# board0.net
KiCad netlist of a schematic drawn in EAGLE
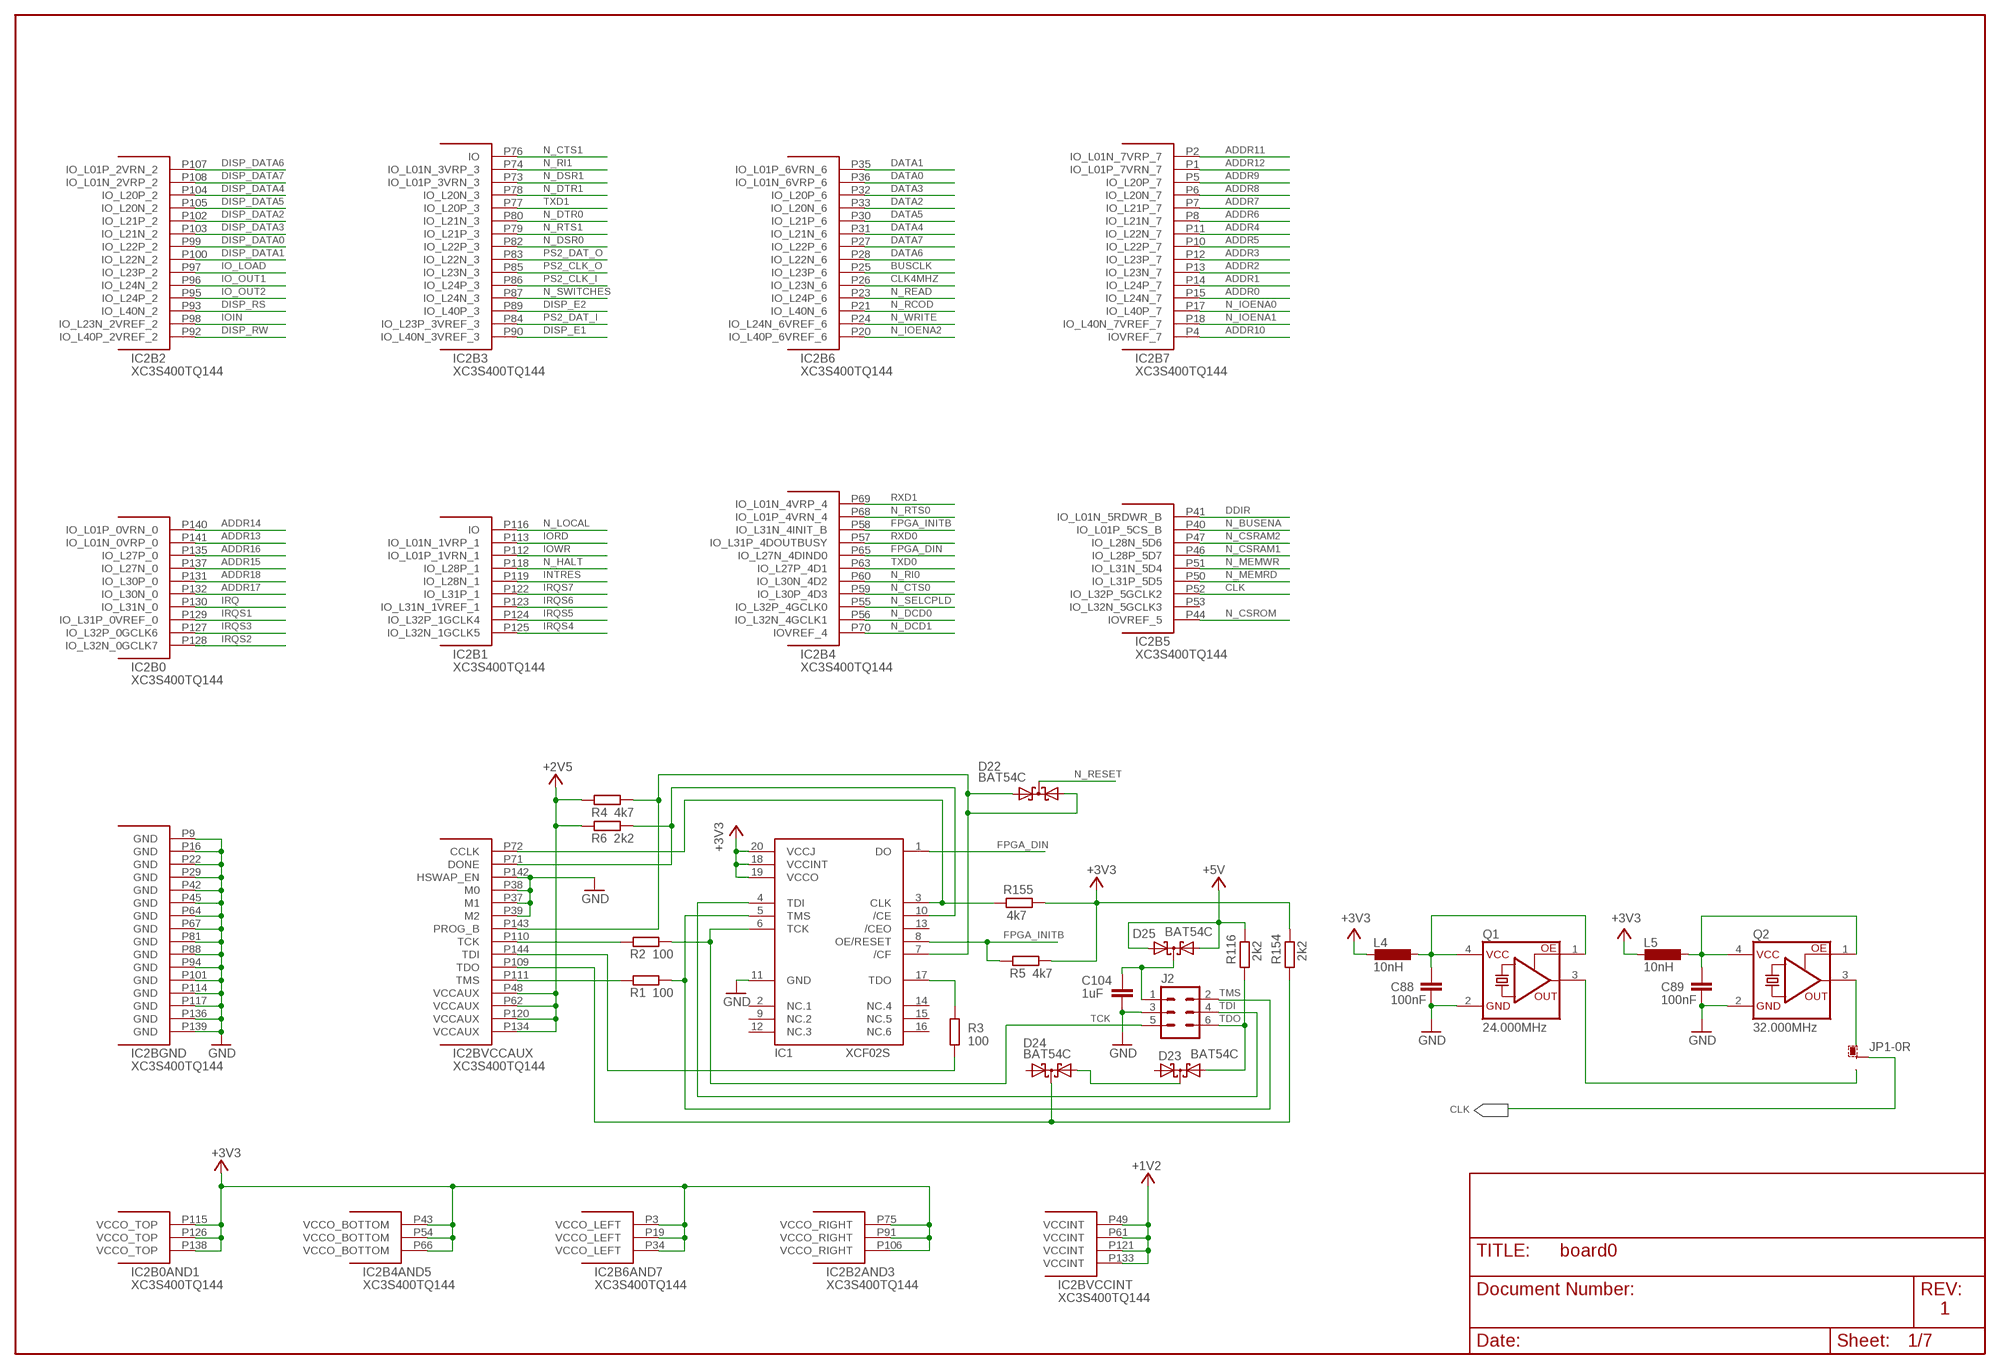
[diagram p0: schematic, sheet 1]
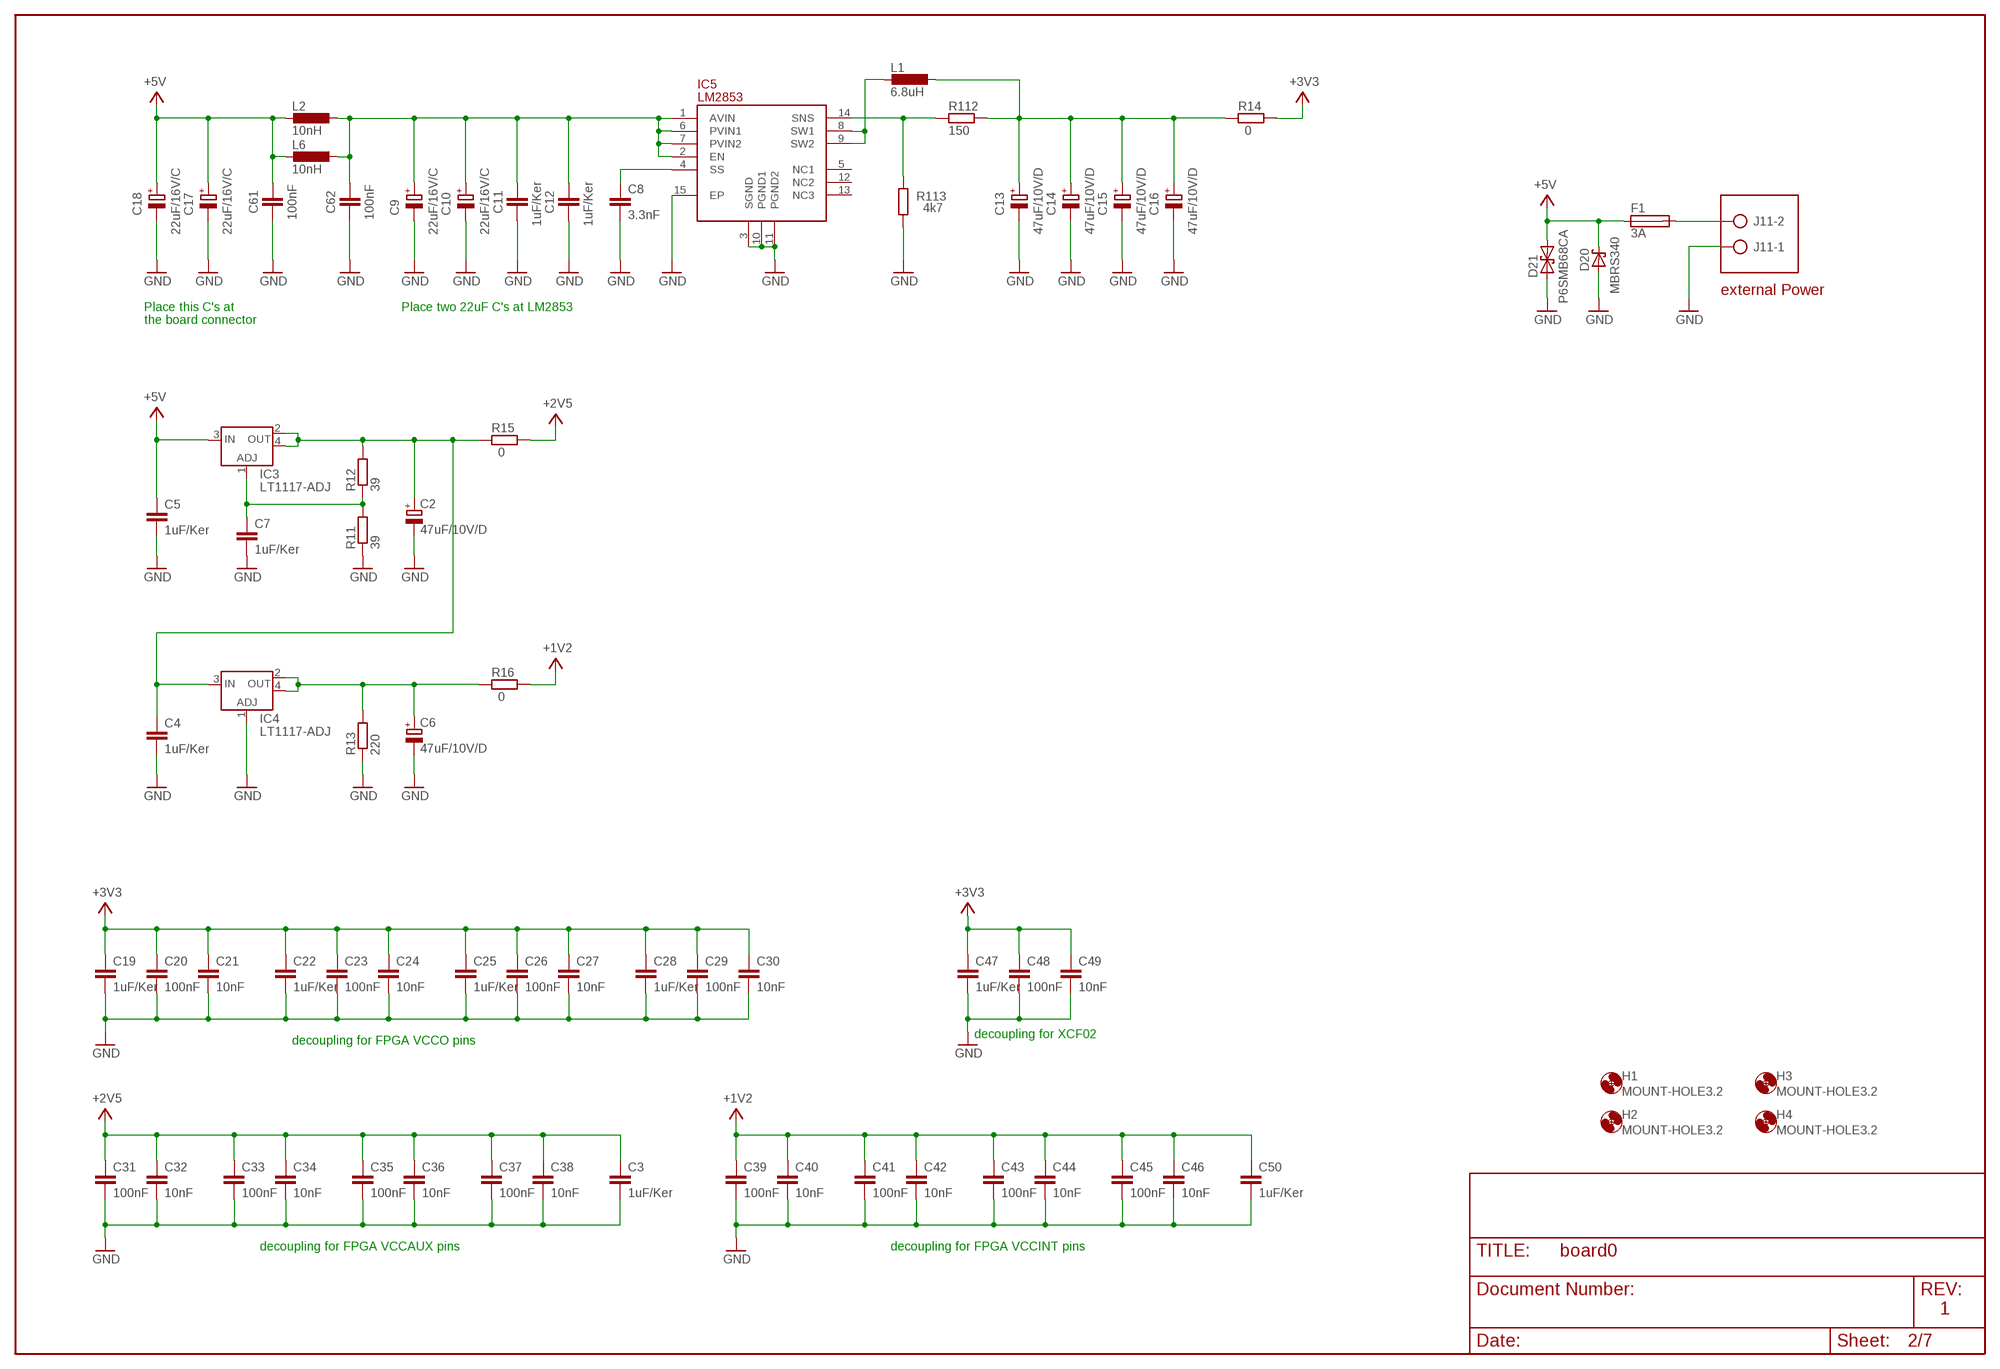
[diagram p1: schematic, sheet 2]
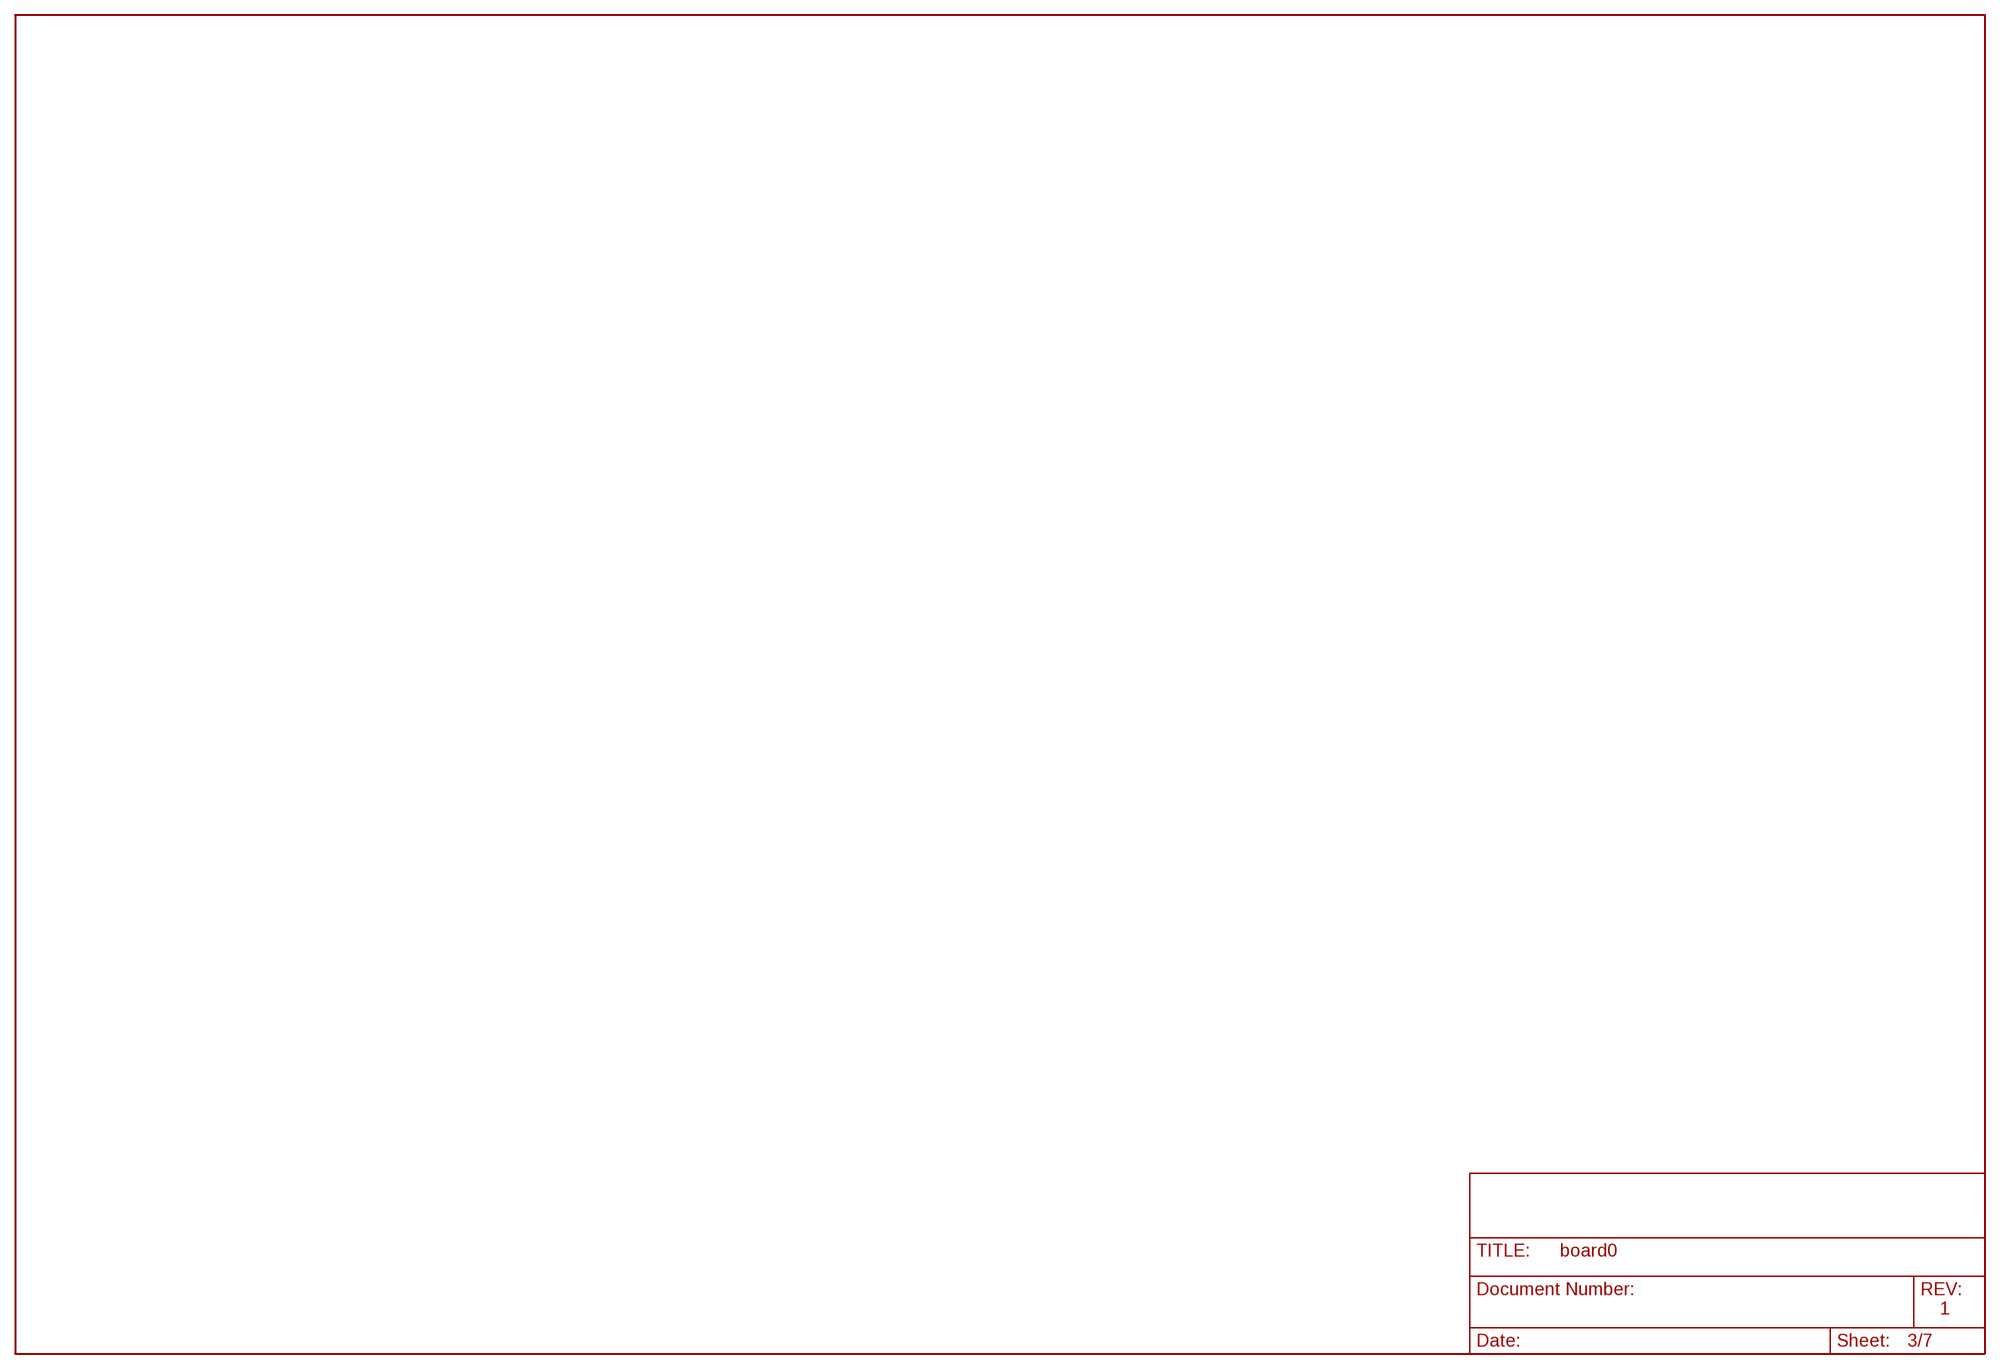
[diagram p2: schematic, sheet 3]
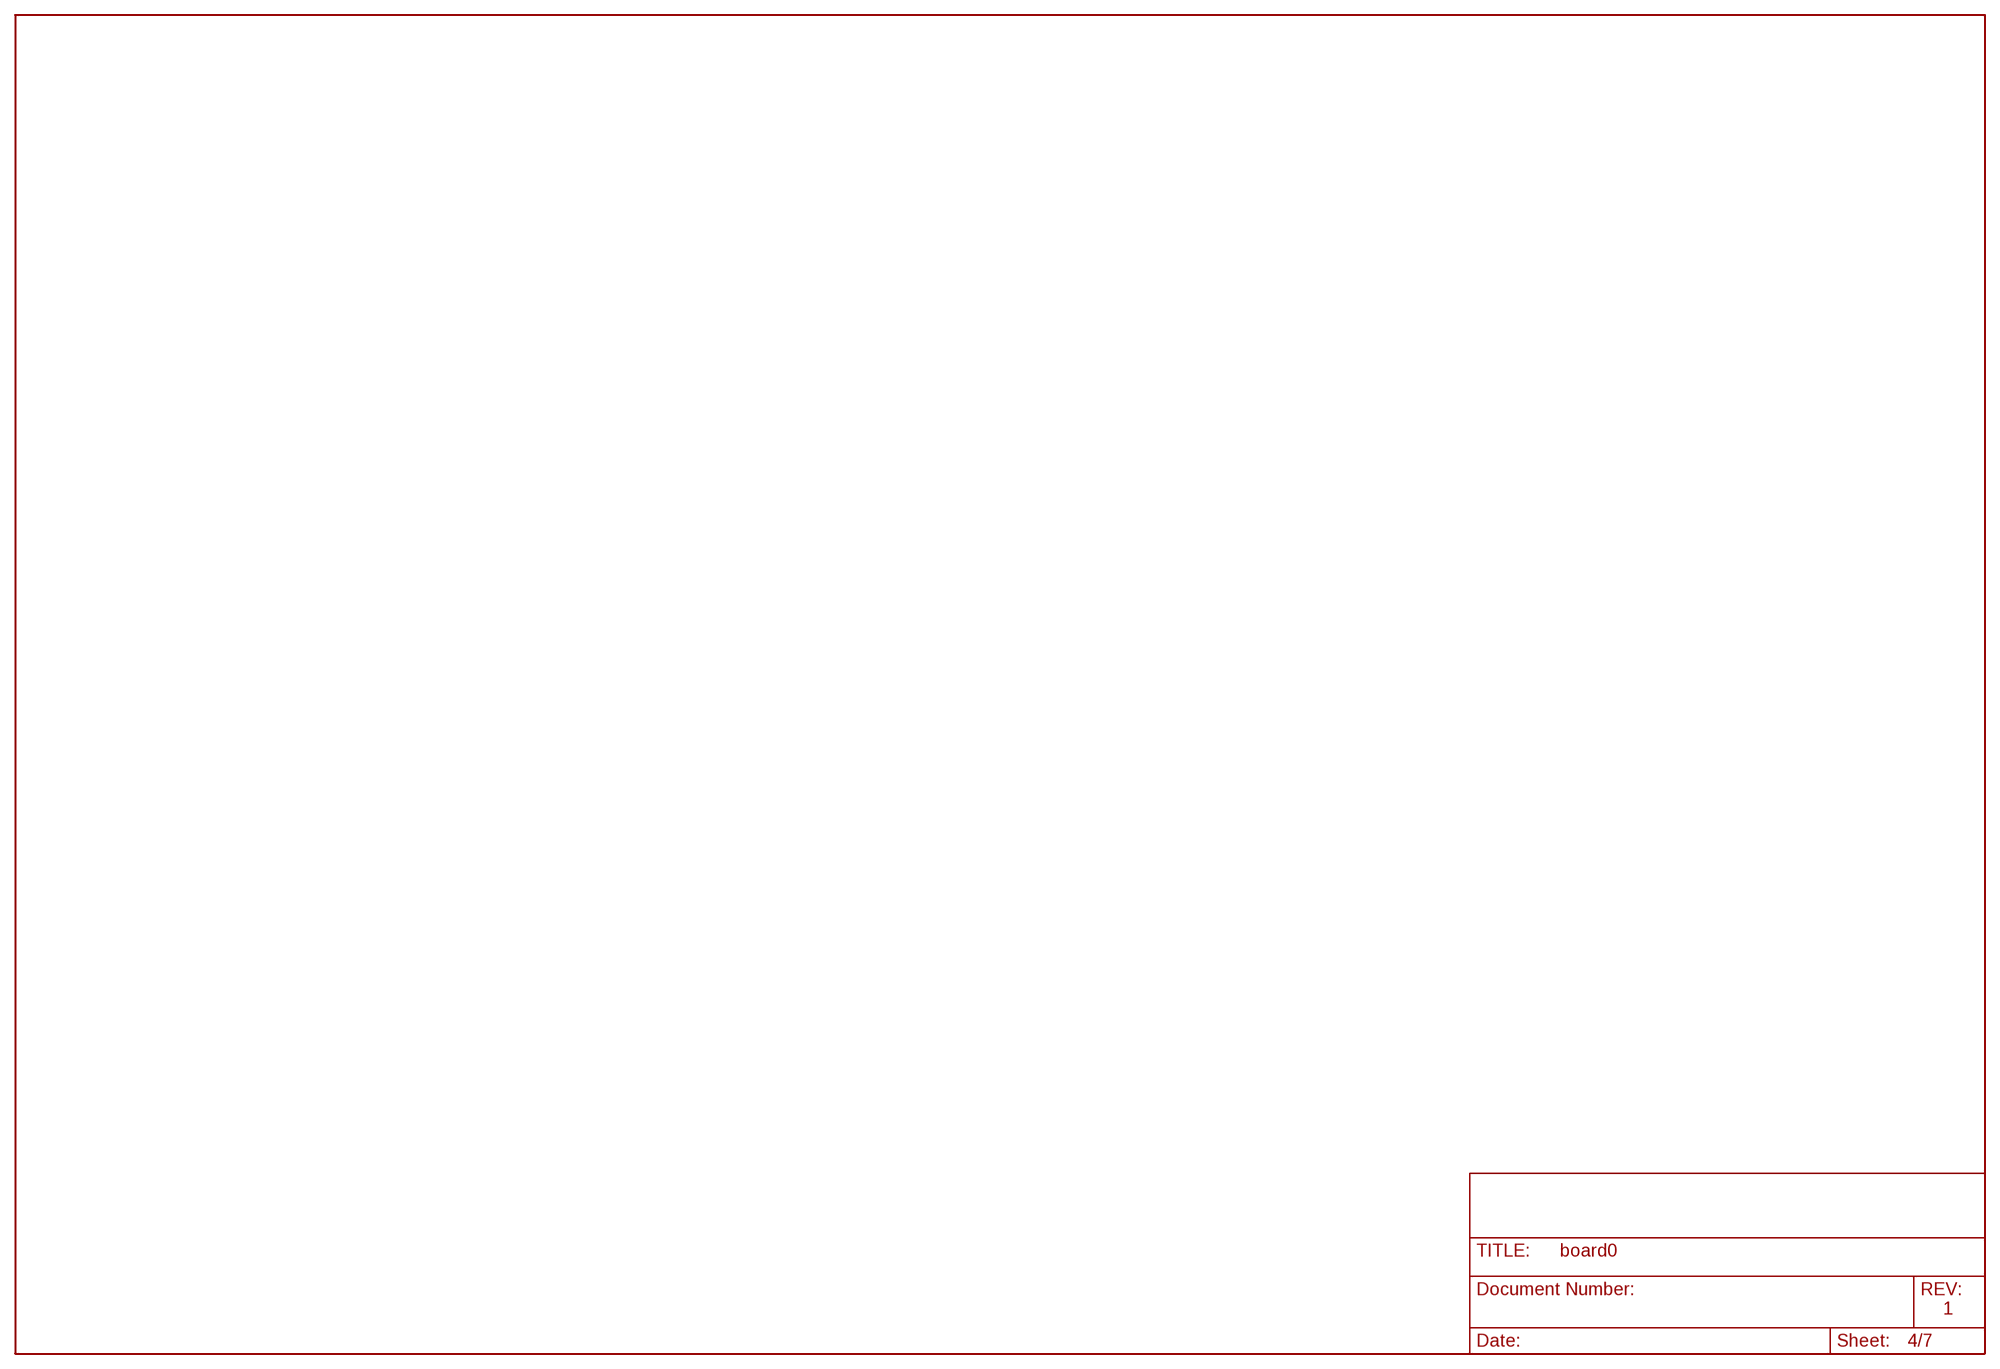
[diagram p3: schematic, sheet 4]
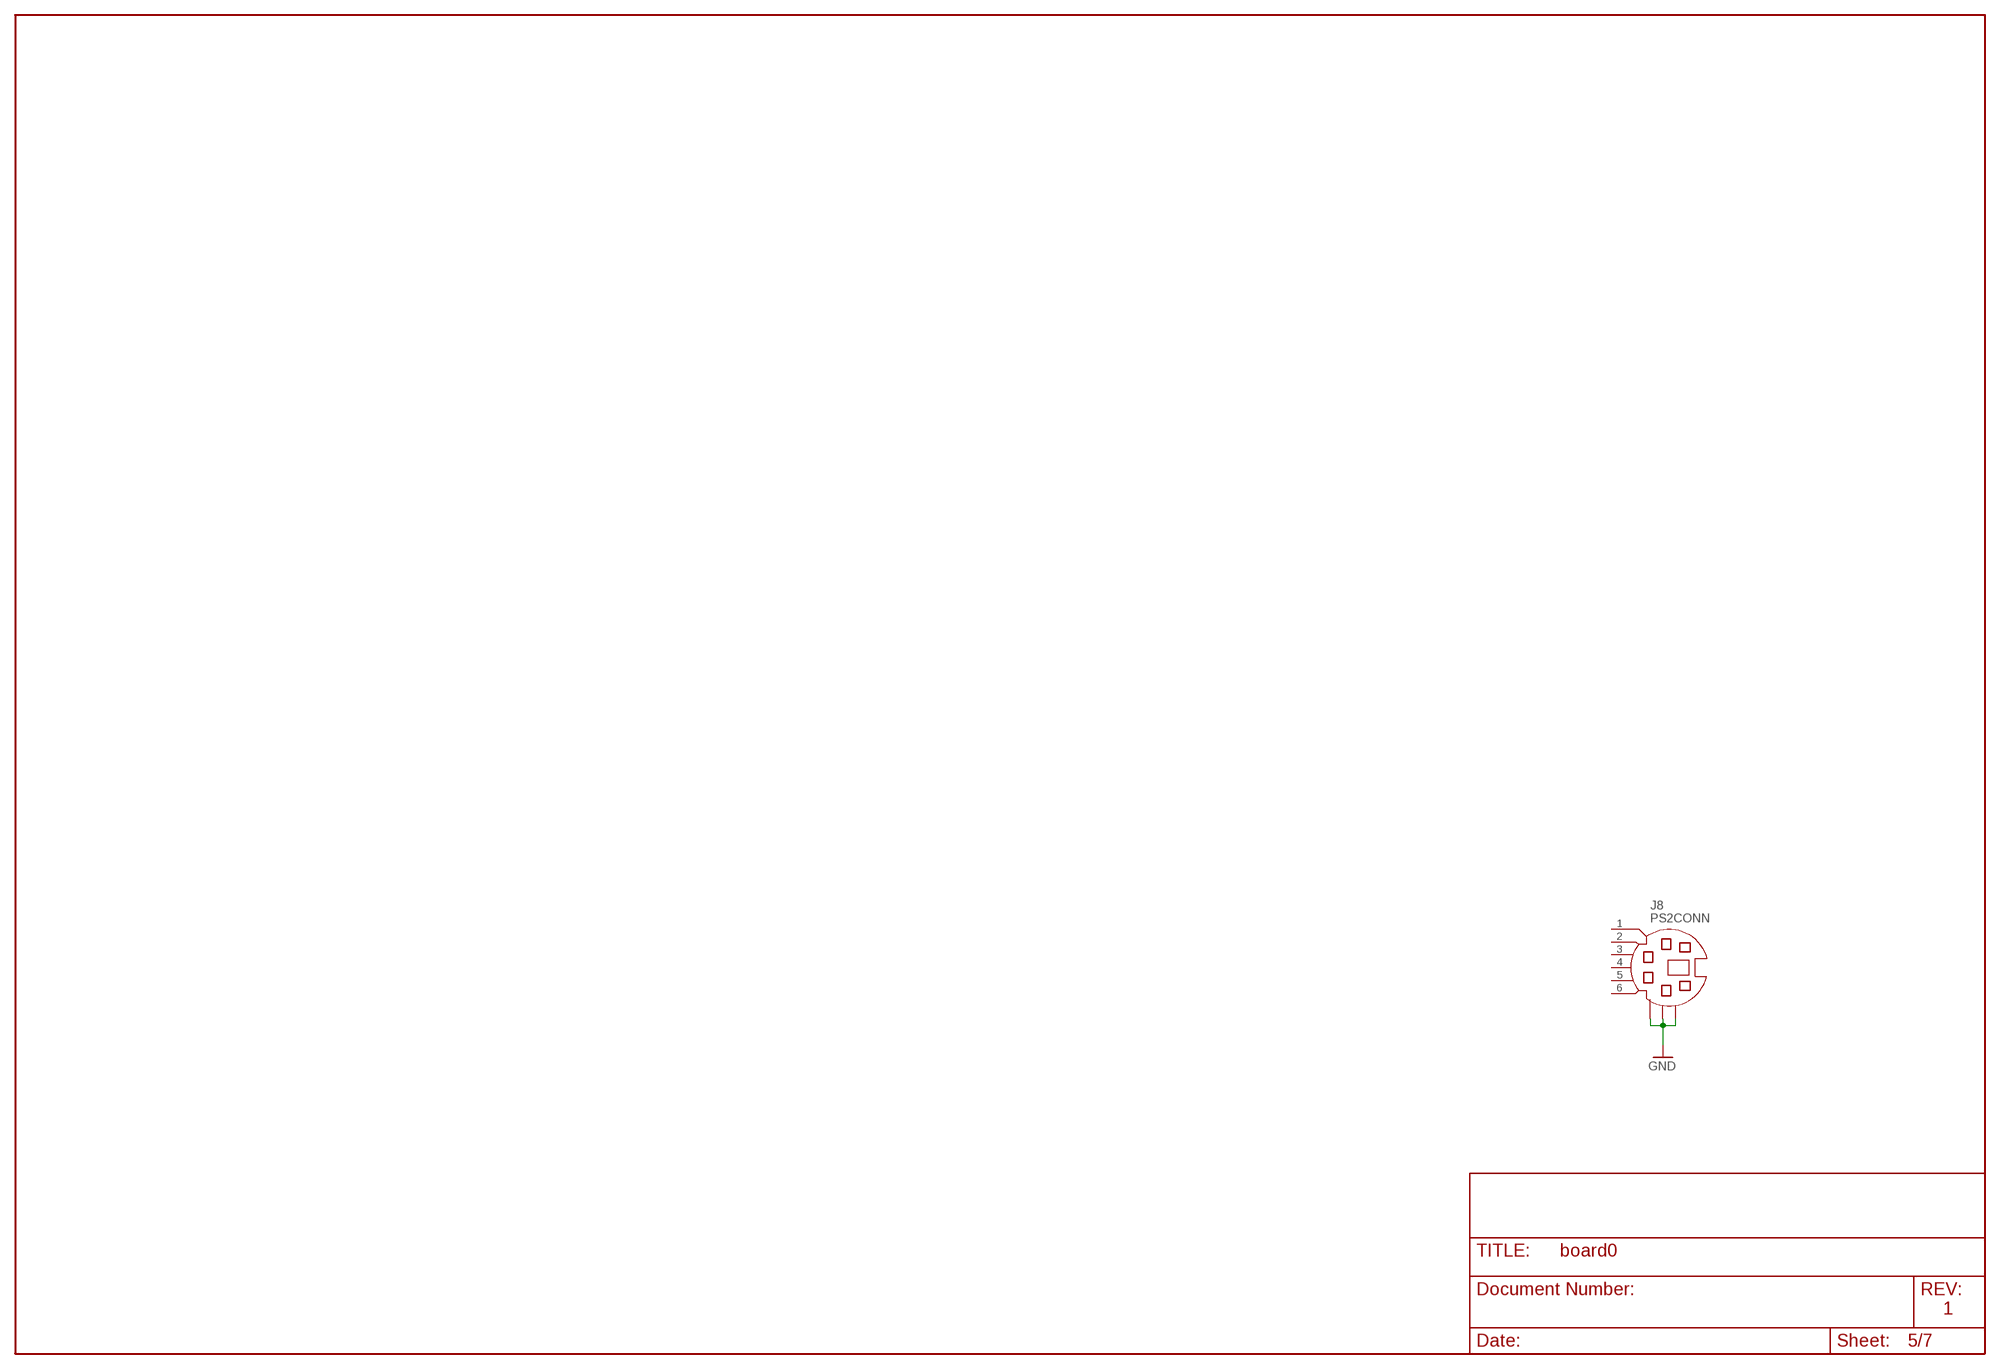
[diagram p4: schematic, sheet 5]
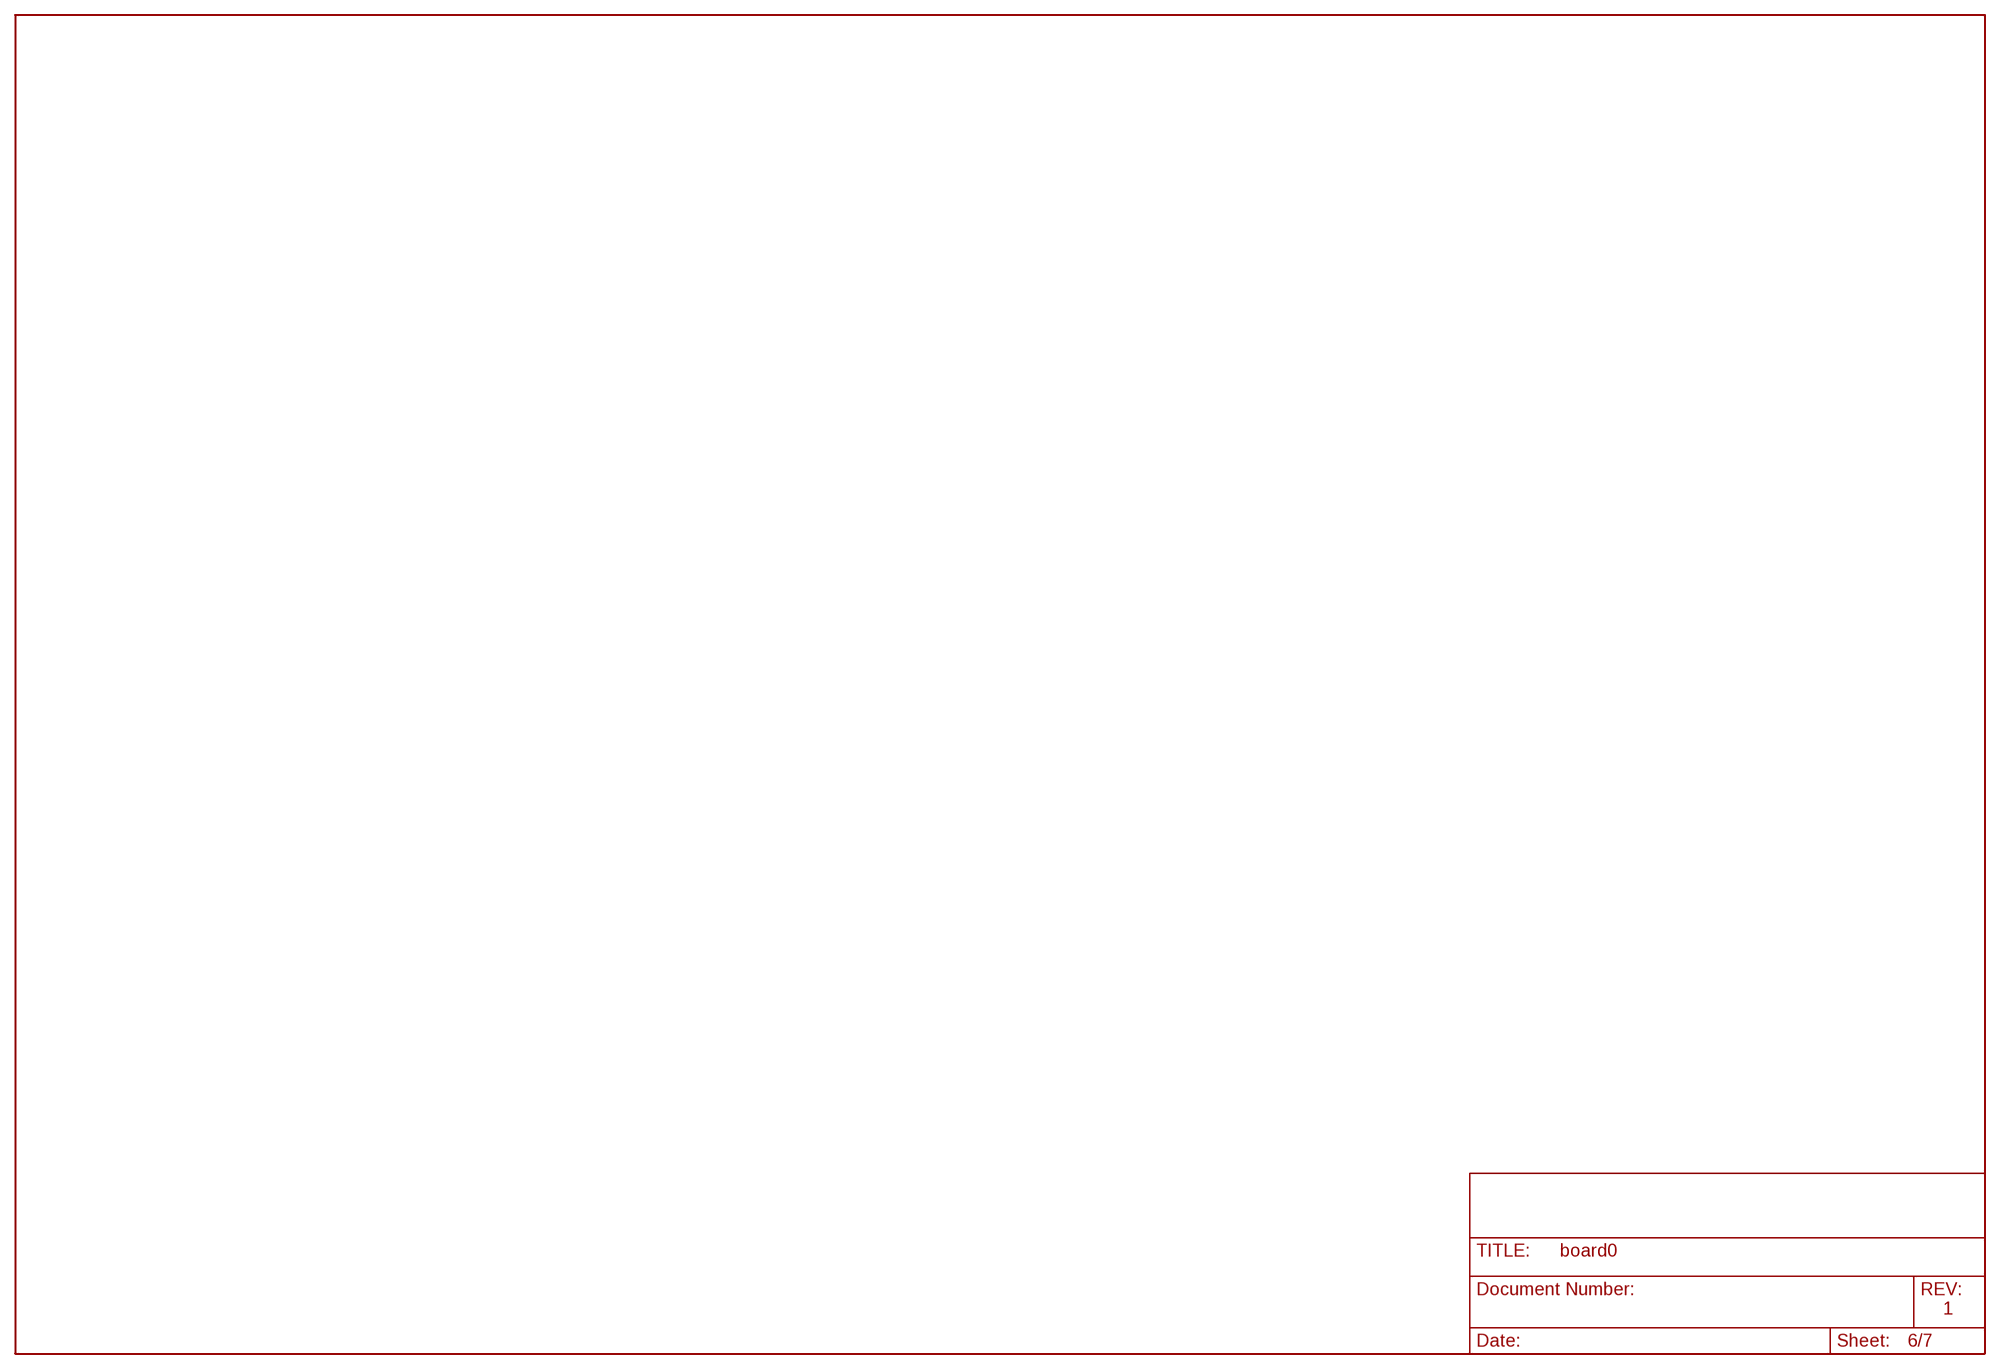
[diagram p5: schematic, sheet 6]
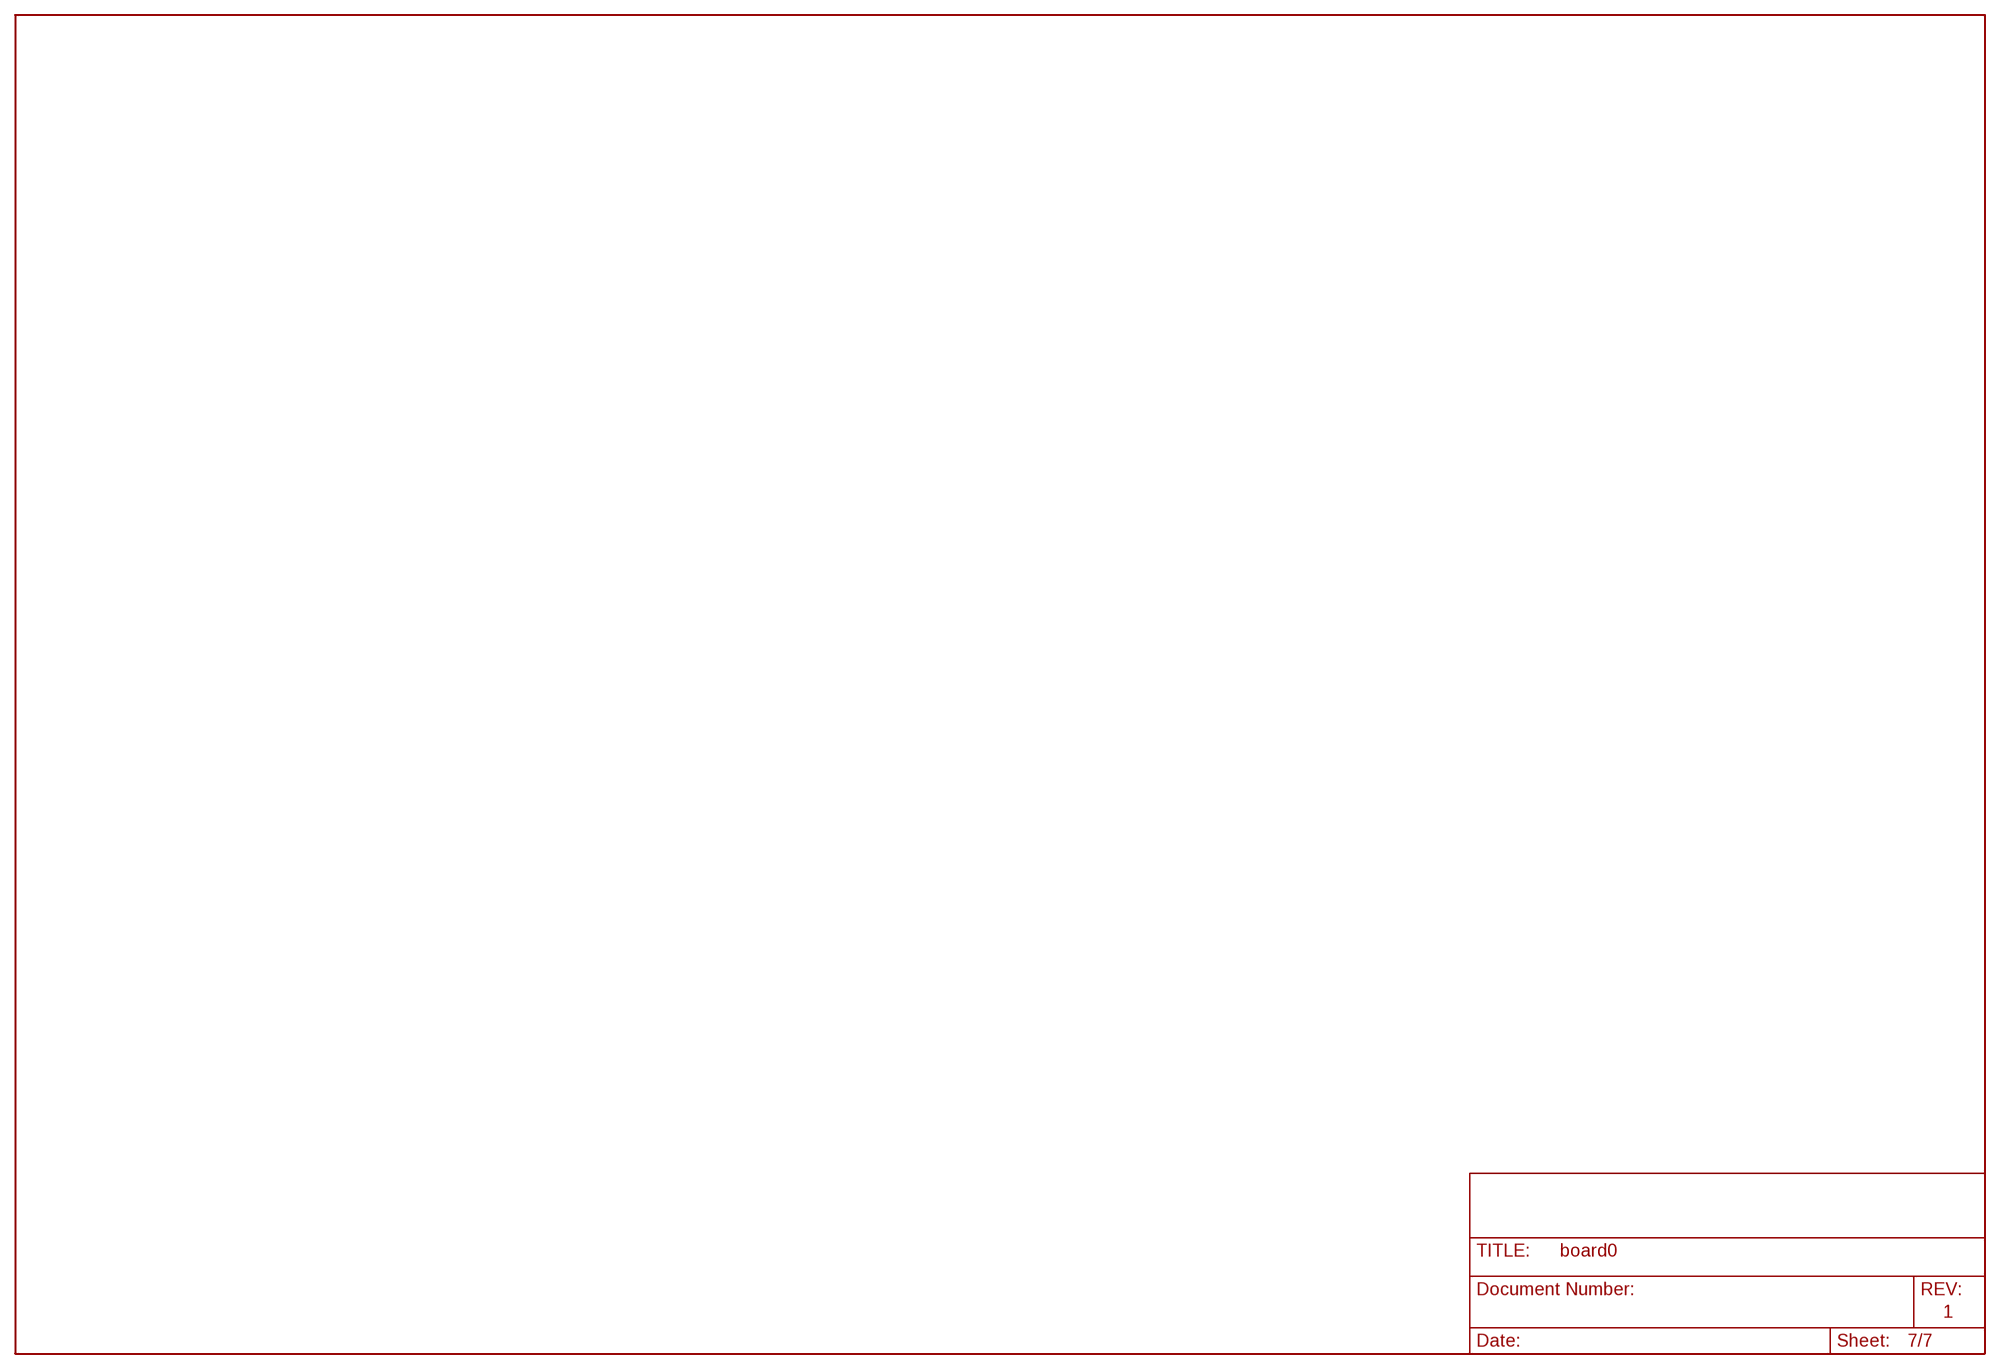
[diagram p6: schematic, sheet 7]

(export (version "E")
  (design (tool "Eeschema 10.0.6"))
  (components
    (comp (ref "C2")
      (value "47uF/10V/D")
      (footprint "eagle-import:D_7343-31R")
      (libsource (lib "eagle-import") (part "CPOL-EUD/7343-31R"))
    )
    (comp (ref "C3")
      (value "1uF/Ker")
      (footprint "eagle-import:C0805")
      (libsource (lib "eagle-import") (part "C-EUC0805"))
    )
    (comp (ref "C4")
      (value "1uF/Ker")
      (footprint "eagle-import:C0805")
      (libsource (lib "eagle-import") (part "C-EUC0805"))
    )
    (comp (ref "C5")
      (value "1uF/Ker")
      (footprint "eagle-import:C0805")
      (libsource (lib "eagle-import") (part "C-EUC0805"))
    )
    (comp (ref "C6")
      (value "47uF/10V/D")
      (footprint "eagle-import:D_7343-31R")
      (libsource (lib "eagle-import") (part "CPOL-EUD/7343-31R"))
    )
    (comp (ref "C7")
      (value "1uF/Ker")
      (footprint "eagle-import:C0805")
      (libsource (lib "eagle-import") (part "C-EUC0805"))
    )
    (comp (ref "C8")
      (value "3.3nF")
      (footprint "eagle-import:C0805")
      (libsource (lib "eagle-import") (part "C-EUC0805"))
    )
    (comp (ref "C9")
      (value "22uF/16V/C")
      (footprint "eagle-import:C_6032-28R")
      (libsource (lib "eagle-import") (part "CPOL-EUC/6032-28R"))
    )
    (comp (ref "C10")
      (value "22uF/16V/C")
      (footprint "eagle-import:C_6032-28R")
      (libsource (lib "eagle-import") (part "CPOL-EUC/6032-28R"))
    )
    (comp (ref "C11")
      (value "1uF/Ker")
      (footprint "eagle-import:C0805")
      (libsource (lib "eagle-import") (part "C-EUC0805"))
    )
    (comp (ref "C12")
      (value "1uF/Ker")
      (footprint "eagle-import:C0805")
      (libsource (lib "eagle-import") (part "C-EUC0805"))
    )
    (comp (ref "C13")
      (value "47uF/10V/D")
      (footprint "eagle-import:D_7343-31R")
      (libsource (lib "eagle-import") (part "CPOL-EUD/7343-31R"))
    )
    (comp (ref "C14")
      (value "47uF/10V/D")
      (footprint "eagle-import:D_7343-31R")
      (libsource (lib "eagle-import") (part "CPOL-EUD/7343-31R"))
    )
    (comp (ref "C15")
      (value "47uF/10V/D")
      (footprint "eagle-import:D_7343-31R")
      (libsource (lib "eagle-import") (part "CPOL-EUD/7343-31R"))
    )
    (comp (ref "C16")
      (value "47uF/10V/D")
      (footprint "eagle-import:D_7343-31R")
      (libsource (lib "eagle-import") (part "CPOL-EUD/7343-31R"))
    )
    (comp (ref "C17")
      (value "22uF/16V/C")
      (footprint "eagle-import:C_6032-28R")
      (libsource (lib "eagle-import") (part "CPOL-EUC/6032-28R"))
    )
    (comp (ref "C18")
      (value "22uF/16V/C")
      (footprint "eagle-import:C_6032-28R")
      (libsource (lib "eagle-import") (part "CPOL-EUC/6032-28R"))
    )
    (comp (ref "C19")
      (value "1uF/Ker")
      (footprint "eagle-import:C0805")
      (libsource (lib "eagle-import") (part "C-EUC0805"))
    )
    (comp (ref "C20")
      (value "100nF")
      (footprint "eagle-import:C0805")
      (libsource (lib "eagle-import") (part "C-EUC0805"))
    )
    (comp (ref "C21")
      (value "10nF")
      (footprint "eagle-import:C0805")
      (libsource (lib "eagle-import") (part "C-EUC0805"))
    )
    (comp (ref "C22")
      (value "1uF/Ker")
      (footprint "eagle-import:C0805")
      (libsource (lib "eagle-import") (part "C-EUC0805"))
    )
    (comp (ref "C23")
      (value "100nF")
      (footprint "eagle-import:C0805")
      (libsource (lib "eagle-import") (part "C-EUC0805"))
    )
    (comp (ref "C24")
      (value "10nF")
      (footprint "eagle-import:C0805")
      (libsource (lib "eagle-import") (part "C-EUC0805"))
    )
    (comp (ref "C25")
      (value "1uF/Ker")
      (footprint "eagle-import:C0805")
      (libsource (lib "eagle-import") (part "C-EUC0805"))
    )
    (comp (ref "C26")
      (value "100nF")
      (footprint "eagle-import:C0805")
      (libsource (lib "eagle-import") (part "C-EUC0805"))
    )
    (comp (ref "C27")
      (value "10nF")
      (footprint "eagle-import:C0805")
      (libsource (lib "eagle-import") (part "C-EUC0805"))
    )
    (comp (ref "C28")
      (value "1uF/Ker")
      (footprint "eagle-import:C0805")
      (libsource (lib "eagle-import") (part "C-EUC0805"))
    )
    (comp (ref "C29")
      (value "100nF")
      (footprint "eagle-import:C0805")
      (libsource (lib "eagle-import") (part "C-EUC0805"))
    )
    (comp (ref "C30")
      (value "10nF")
      (footprint "eagle-import:C0805")
      (libsource (lib "eagle-import") (part "C-EUC0805"))
    )
    (comp (ref "C31")
      (value "100nF")
      (footprint "eagle-import:C0805")
      (libsource (lib "eagle-import") (part "C-EUC0805"))
    )
    (comp (ref "C32")
      (value "10nF")
      (footprint "eagle-import:C0805")
      (libsource (lib "eagle-import") (part "C-EUC0805"))
    )
    (comp (ref "C33")
      (value "100nF")
      (footprint "eagle-import:C0805")
      (libsource (lib "eagle-import") (part "C-EUC0805"))
    )
    (comp (ref "C34")
      (value "10nF")
      (footprint "eagle-import:C0805")
      (libsource (lib "eagle-import") (part "C-EUC0805"))
    )
    (comp (ref "C35")
      (value "100nF")
      (footprint "eagle-import:C0805")
      (libsource (lib "eagle-import") (part "C-EUC0805"))
    )
    (comp (ref "C36")
      (value "10nF")
      (footprint "eagle-import:C0805")
      (libsource (lib "eagle-import") (part "C-EUC0805"))
    )
    (comp (ref "C37")
      (value "100nF")
      (footprint "eagle-import:C0805")
      (libsource (lib "eagle-import") (part "C-EUC0805"))
    )
    (comp (ref "C38")
      (value "10nF")
      (footprint "eagle-import:C0805")
      (libsource (lib "eagle-import") (part "C-EUC0805"))
    )
    (comp (ref "C39")
      (value "100nF")
      (footprint "eagle-import:C0805")
      (libsource (lib "eagle-import") (part "C-EUC0805"))
    )
    (comp (ref "C40")
      (value "10nF")
      (footprint "eagle-import:C0805")
      (libsource (lib "eagle-import") (part "C-EUC0805"))
    )
    (comp (ref "C41")
      (value "100nF")
      (footprint "eagle-import:C0805")
      (libsource (lib "eagle-import") (part "C-EUC0805"))
    )
    (comp (ref "C42")
      (value "10nF")
      (footprint "eagle-import:C0805")
      (libsource (lib "eagle-import") (part "C-EUC0805"))
    )
    (comp (ref "C43")
      (value "100nF")
      (footprint "eagle-import:C0805")
      (libsource (lib "eagle-import") (part "C-EUC0805"))
    )
    (comp (ref "C44")
      (value "10nF")
      (footprint "eagle-import:C0805")
      (libsource (lib "eagle-import") (part "C-EUC0805"))
    )
    (comp (ref "C45")
      (value "100nF")
      (footprint "eagle-import:C0805")
      (libsource (lib "eagle-import") (part "C-EUC0805"))
    )
    (comp (ref "C46")
      (value "10nF")
      (footprint "eagle-import:C0805")
      (libsource (lib "eagle-import") (part "C-EUC0805"))
    )
    (comp (ref "C47")
      (value "1uF/Ker")
      (footprint "eagle-import:C0805")
      (libsource (lib "eagle-import") (part "C-EUC0805"))
    )
    (comp (ref "C48")
      (value "100nF")
      (footprint "eagle-import:C0805")
      (libsource (lib "eagle-import") (part "C-EUC0805"))
    )
    (comp (ref "C49")
      (value "10nF")
      (footprint "eagle-import:C0805")
      (libsource (lib "eagle-import") (part "C-EUC0805"))
    )
    (comp (ref "C50")
      (value "1uF/Ker")
      (footprint "eagle-import:C0805")
      (libsource (lib "eagle-import") (part "C-EUC0805"))
    )
    (comp (ref "C61")
      (value "100nF")
      (footprint "eagle-import:C0805")
      (libsource (lib "eagle-import") (part "C-EUC0805"))
    )
    (comp (ref "C62")
      (value "100nF")
      (footprint "eagle-import:C0805")
      (libsource (lib "eagle-import") (part "C-EUC0805"))
    )
    (comp (ref "D20")
      (value "MBRS340")
      (footprint "eagle-import:DO214AB")
      (libsource (lib "eagle-import") (part "MBRS340"))
    )
    (comp (ref "D21")
      (value "P6SMB68CA")
      (footprint "eagle-import:DO214AA")
      (libsource (lib "eagle-import") (part "P6SMB68CA"))
    )
    (comp (ref "F1")
      (value "3A")
      (footprint "eagle-import:HASF")
      (libsource (lib "eagle-import") (part "FUSE-HASF"))
    )
    (comp (ref "H1")
      (value "MOUNT-HOLE3.2")
      (footprint "eagle-import:3,2")
      (libsource (lib "eagle-import") (part "MOUNT-HOLE3.2"))
    )
    (comp (ref "H2")
      (value "MOUNT-HOLE3.2")
      (footprint "eagle-import:3,2")
      (libsource (lib "eagle-import") (part "MOUNT-HOLE3.2"))
    )
    (comp (ref "H3")
      (value "MOUNT-HOLE3.2")
      (footprint "eagle-import:3,2")
      (libsource (lib "eagle-import") (part "MOUNT-HOLE3.2"))
    )
    (comp (ref "H4")
      (value "MOUNT-HOLE3.2")
      (footprint "eagle-import:3,2")
      (libsource (lib "eagle-import") (part "MOUNT-HOLE3.2"))
    )
    (comp (ref "IC3")
      (value "LT1117-ADJ")
      (footprint "eagle-import:SOT223")
      (libsource (lib "eagle-import") (part "LT1117-ADJ"))
    )
    (comp (ref "IC4")
      (value "LT1117-ADJ")
      (footprint "eagle-import:SOT223")
      (libsource (lib "eagle-import") (part "LT1117-ADJ"))
    )
    (comp (ref "IC5")
      (value "LM2853")
      (footprint "eagle-import:ETSSOP14")
      (libsource (lib "eagle-import") (part "LM2853"))
    )
    (comp (ref "J11")
      (value "AK500/2")
      (footprint "eagle-import:AK500_2")
      (libsource (lib "eagle-import") (part "AK500/2"))
    )
    (comp (ref "L1")
      (value "6.8uH")
      (footprint "eagle-import:DO3316P")
      (libsource (lib "eagle-import") (part "DO3316P"))
    )
    (comp (ref "L2")
      (value "10nH")
      (footprint "eagle-import:0805")
      (libsource (lib "eagle-import") (part "smd-special_L-0805"))
    )
    (comp (ref "L6")
      (value "10nH")
      (footprint "eagle-import:0805")
      (libsource (lib "eagle-import") (part "smd-special_L-0805"))
    )
    (comp (ref "R11")
      (value "39")
      (footprint "eagle-import:R0805")
      (libsource (lib "eagle-import") (part "R-EU_R0805"))
    )
    (comp (ref "R12")
      (value "39")
      (footprint "eagle-import:R0805")
      (libsource (lib "eagle-import") (part "R-EU_R0805"))
    )
    (comp (ref "R13")
      (value "220")
      (footprint "eagle-import:R0805")
      (libsource (lib "eagle-import") (part "R-EU_R0805"))
    )
    (comp (ref "R14")
      (value "0")
      (footprint "eagle-import:R0805")
      (libsource (lib "eagle-import") (part "R-EU_R0805"))
    )
    (comp (ref "R15")
      (value "0")
      (footprint "eagle-import:R0805")
      (libsource (lib "eagle-import") (part "R-EU_R0805"))
    )
    (comp (ref "R16")
      (value "0")
      (footprint "eagle-import:R0805")
      (libsource (lib "eagle-import") (part "R-EU_R0805"))
    )
    (comp (ref "R112")
      (value "150")
      (footprint "eagle-import:R0805")
      (libsource (lib "eagle-import") (part "R-EU_R0805"))
    )
    (comp (ref "R113")
      (value "4k7")
      (footprint "eagle-import:R0805")
      (libsource (lib "eagle-import") (part "R-EU_R0805"))
    )
    (comp (ref "J8")
      (value "PS2CONN")
      (footprint "eagle-import:MINIDIN-6")
      (libsource (lib "eagle-import") (part "PS2CONN"))
    )
    (comp (ref "C88")
      (value "100nF")
      (footprint "eagle-import:C0805")
      (libsource (lib "eagle-import") (part "C-EUC0805"))
    )
    (comp (ref "C89")
      (value "100nF")
      (footprint "eagle-import:C0805")
      (libsource (lib "eagle-import") (part "C-EUC0805"))
    )
    (comp (ref "C104")
      (value "1uF")
      (footprint "eagle-import:C0805")
      (libsource (lib "eagle-import") (part "C-EUC0805"))
    )
    (comp (ref "D22")
      (value "BAT54C")
      (footprint "eagle-import:SOT23")
      (libsource (lib "eagle-import") (part "BAS40-05"))
    )
    (comp (ref "D23")
      (value "BAT54C")
      (footprint "eagle-import:SOT23")
      (libsource (lib "eagle-import") (part "BAS40-05"))
    )
    (comp (ref "D24")
      (value "BAT54C")
      (footprint "eagle-import:SOT23")
      (libsource (lib "eagle-import") (part "BAS40-05"))
    )
    (comp (ref "D25")
      (value "BAT54C")
      (footprint "eagle-import:SOT23")
      (libsource (lib "eagle-import") (part "BAS40-05"))
    )
    (comp (ref "IC1")
      (value "XCF02S")
      (footprint "eagle-import:VO20")
      (libsource (lib "eagle-import") (part "XCF02S"))
    )
    (comp (ref "IC2")
      (value "XC3S400TQ144")
      (footprint "eagle-import:TQ144")
      (libsource (lib "eagle-import") (part "XC3S400TQ144"))
    )
    (comp (ref "J2")
      (value "ML6")
      (footprint "eagle-import:ML6")
      (libsource (lib "eagle-import") (part "ML6"))
    )
    (comp (ref "JP1")
      (value "0R-JUMPA")
      (footprint "eagle-import:A0R-JMP")
      (libsource (lib "eagle-import") (part "0R-JUMPA"))
    )
    (comp (ref "L4")
      (value "10nH")
      (footprint "eagle-import:0805")
      (libsource (lib "eagle-import") (part "L-0805"))
    )
    (comp (ref "L5")
      (value "10nH")
      (footprint "eagle-import:0805")
      (libsource (lib "eagle-import") (part "L-0805"))
    )
    (comp (ref "Q1")
      (value "24.000MHz")
      (footprint "eagle-import:XO91")
      (libsource (lib "eagle-import") (part "XO91"))
    )
    (comp (ref "Q2")
      (value "32.000MHz")
      (footprint "eagle-import:XO91")
      (libsource (lib "eagle-import") (part "XO91"))
    )
    (comp (ref "R1")
      (value "100")
      (footprint "eagle-import:M0805")
      (libsource (lib "eagle-import") (part "R-EU_M0805"))
    )
    (comp (ref "R2")
      (value "100")
      (footprint "eagle-import:M0805")
      (libsource (lib "eagle-import") (part "R-EU_M0805"))
    )
    (comp (ref "R3")
      (value "100")
      (footprint "eagle-import:M0805")
      (libsource (lib "eagle-import") (part "R-EU_M0805"))
    )
    (comp (ref "R4")
      (value "4k7")
      (footprint "eagle-import:M0805")
      (libsource (lib "eagle-import") (part "R-EU_M0805"))
    )
    (comp (ref "R5")
      (value "4k7")
      (footprint "eagle-import:M0805")
      (libsource (lib "eagle-import") (part "R-EU_M0805"))
    )
    (comp (ref "R6")
      (value "2k2")
      (footprint "eagle-import:M0805")
      (libsource (lib "eagle-import") (part "R-EU_M0805"))
    )
    (comp (ref "R116")
      (value "2k2")
      (footprint "eagle-import:M0805")
      (libsource (lib "eagle-import") (part "R-EU_M0805"))
    )
    (comp (ref "R154")
      (value "2k2")
      (footprint "eagle-import:M0805")
      (libsource (lib "eagle-import") (part "R-EU_M0805"))
    )
    (comp (ref "R155")
      (value "4k7")
      (footprint "eagle-import:M0805")
      (libsource (lib "eagle-import") (part "R-EU_M0805"))
    )
  )
  (nets
    (net (code "1") (name "+1V2") (class "Default")
      (node (ref "C39") (pin "1") (pinfunction "1_1") (pintype "passive"))
      (node (ref "C40") (pin "1") (pinfunction "1_1") (pintype "passive"))
      (node (ref "C41") (pin "1") (pinfunction "1_1") (pintype "passive"))
      (node (ref "C42") (pin "1") (pinfunction "1_1") (pintype "passive"))
      (node (ref "C43") (pin "1") (pinfunction "1_1") (pintype "passive"))
      (node (ref "C44") (pin "1") (pinfunction "1_1") (pintype "passive"))
      (node (ref "C45") (pin "1") (pinfunction "1_1") (pintype "passive"))
      (node (ref "C46") (pin "1") (pinfunction "1_1") (pintype "passive"))
      (node (ref "C50") (pin "1") (pinfunction "1_1") (pintype "passive"))
      (node (ref "IC2") (pin "P121") (pinfunction "VCCINT_P121") (pintype "input"))
      (node (ref "IC2") (pin "P133") (pinfunction "VCCINT_P133") (pintype "input"))
      (node (ref "IC2") (pin "P49") (pinfunction "VCCINT_P49") (pintype "input"))
      (node (ref "IC2") (pin "P61") (pinfunction "VCCINT_P61") (pintype "input"))
      (node (ref "R16") (pin "2") (pinfunction "2_2") (pintype "passive"))
    )
    (net (code "2") (name "+2V5") (class "Default")
      (node (ref "C3") (pin "1") (pinfunction "1_1") (pintype "passive"))
      (node (ref "C31") (pin "1") (pinfunction "1_1") (pintype "passive"))
      (node (ref "C32") (pin "1") (pinfunction "1_1") (pintype "passive"))
      (node (ref "C33") (pin "1") (pinfunction "1_1") (pintype "passive"))
      (node (ref "C34") (pin "1") (pinfunction "1_1") (pintype "passive"))
      (node (ref "C35") (pin "1") (pinfunction "1_1") (pintype "passive"))
      (node (ref "C36") (pin "1") (pinfunction "1_1") (pintype "passive"))
      (node (ref "C37") (pin "1") (pinfunction "1_1") (pintype "passive"))
      (node (ref "C38") (pin "1") (pinfunction "1_1") (pintype "passive"))
      (node (ref "IC2") (pin "P120") (pinfunction "VCCAUX_P120") (pintype "input"))
      (node (ref "IC2") (pin "P134") (pinfunction "VCCAUX_P134") (pintype "input"))
      (node (ref "IC2") (pin "P48") (pinfunction "VCCAUX_P48") (pintype "input"))
      (node (ref "IC2") (pin "P62") (pinfunction "VCCAUX_P62") (pintype "input"))
      (node (ref "R15") (pin "2") (pinfunction "2_2") (pintype "passive"))
      (node (ref "R4") (pin "1") (pinfunction "1_1") (pintype "passive"))
      (node (ref "R6") (pin "1") (pinfunction "1_1") (pintype "passive"))
    )
    (net (code "3") (name "+3V3") (class "Default")
      (node (ref "C19") (pin "1") (pinfunction "1_1") (pintype "passive"))
      (node (ref "C20") (pin "1") (pinfunction "1_1") (pintype "passive"))
      (node (ref "C21") (pin "1") (pinfunction "1_1") (pintype "passive"))
      (node (ref "C22") (pin "1") (pinfunction "1_1") (pintype "passive"))
      (node (ref "C23") (pin "1") (pinfunction "1_1") (pintype "passive"))
      (node (ref "C24") (pin "1") (pinfunction "1_1") (pintype "passive"))
      (node (ref "C25") (pin "1") (pinfunction "1_1") (pintype "passive"))
      (node (ref "C26") (pin "1") (pinfunction "1_1") (pintype "passive"))
      (node (ref "C27") (pin "1") (pinfunction "1_1") (pintype "passive"))
      (node (ref "C28") (pin "1") (pinfunction "1_1") (pintype "passive"))
      (node (ref "C29") (pin "1") (pinfunction "1_1") (pintype "passive"))
      (node (ref "C30") (pin "1") (pinfunction "1_1") (pintype "passive"))
      (node (ref "C47") (pin "1") (pinfunction "1_1") (pintype "passive"))
      (node (ref "C48") (pin "1") (pinfunction "1_1") (pintype "passive"))
      (node (ref "C49") (pin "1") (pinfunction "1_1") (pintype "passive"))
      (node (ref "IC1") (pin "18") (pinfunction "VCCINT_18") (pintype "bidirectional"))
      (node (ref "IC1") (pin "19") (pinfunction "VCCO_19") (pintype "bidirectional"))
      (node (ref "IC1") (pin "20") (pinfunction "VCCJ_20") (pintype "bidirectional"))
      (node (ref "IC2") (pin "P106") (pinfunction "VCCO_RIGHT_P106") (pintype "input"))
      (node (ref "IC2") (pin "P115") (pinfunction "VCCO_TOP_P115") (pintype "input"))
      (node (ref "IC2") (pin "P126") (pinfunction "VCCO_TOP_P126") (pintype "input"))
      (node (ref "IC2") (pin "P138") (pinfunction "VCCO_TOP_P138") (pintype "input"))
      (node (ref "IC2") (pin "P19") (pinfunction "VCCO_LEFT_P19") (pintype "input"))
      (node (ref "IC2") (pin "P3") (pinfunction "VCCO_LEFT_P3") (pintype "input"))
      (node (ref "IC2") (pin "P34") (pinfunction "VCCO_LEFT_P34") (pintype "input"))
      (node (ref "IC2") (pin "P43") (pinfunction "VCCO_BOTTOM_P43") (pintype "input"))
      (node (ref "IC2") (pin "P54") (pinfunction "VCCO_BOTTOM_P54") (pintype "input"))
      (node (ref "IC2") (pin "P66") (pinfunction "VCCO_BOTTOM_P66") (pintype "input"))
      (node (ref "IC2") (pin "P75") (pinfunction "VCCO_RIGHT_P75") (pintype "input"))
      (node (ref "IC2") (pin "P91") (pinfunction "VCCO_RIGHT_P91") (pintype "input"))
      (node (ref "L4") (pin "2") (pinfunction "2_2") (pintype "passive"))
      (node (ref "L5") (pin "2") (pinfunction "2_2") (pintype "passive"))
      (node (ref "R14") (pin "2") (pinfunction "2_2") (pintype "passive"))
      (node (ref "R154") (pin "2") (pinfunction "2_2") (pintype "passive"))
      (node (ref "R155") (pin "2") (pinfunction "2_2") (pintype "passive"))
      (node (ref "R5") (pin "2") (pinfunction "2_2") (pintype "passive"))
    )
    (net (code "4") (name "+5V") (class "Default")
      (node (ref "C17") (pin "+") (pinfunction "+_+") (pintype "passive"))
      (node (ref "C18") (pin "+") (pinfunction "+_+") (pintype "passive"))
      (node (ref "C5") (pin "1") (pinfunction "1_1") (pintype "passive"))
      (node (ref "C61") (pin "1") (pinfunction "1_1") (pintype "passive"))
      (node (ref "D20") (pin "K") (pinfunction "C_K") (pintype "passive"))
      (node (ref "D21") (pin "K") (pinfunction "C_K") (pintype "passive"))
      (node (ref "D25") (pin "1") (pinfunction "A1_1") (pintype "passive"))
      (node (ref "D25") (pin "2") (pinfunction "A2_2") (pintype "passive"))
      (node (ref "F1") (pin "1") (pinfunction "1_1") (pintype "passive"))
      (node (ref "IC3") (pin "3") (pinfunction "IN_3") (pintype "input"))
      (node (ref "L2") (pin "2") (pinfunction "2_2") (pintype "passive"))
      (node (ref "L6") (pin "2") (pinfunction "2_2") (pintype "passive"))
      (node (ref "R116") (pin "2") (pinfunction "2_2") (pintype "passive"))
    )
    (net (code "5") (name "ADDR0") (class "Default")
      (node (ref "IC2") (pin "P15") (pinfunction "IO_L24N_7_P15") (pintype "bidirectional"))
    )
    (net (code "6") (name "ADDR1") (class "Default")
      (node (ref "IC2") (pin "P14") (pinfunction "IO_L24P_7_P14") (pintype "bidirectional"))
    )
    (net (code "7") (name "ADDR2") (class "Default")
      (node (ref "IC2") (pin "P13") (pinfunction "IO_L23N_7_P13") (pintype "bidirectional"))
    )
    (net (code "8") (name "ADDR3") (class "Default")
      (node (ref "IC2") (pin "P12") (pinfunction "IO_L23P_7_P12") (pintype "bidirectional"))
    )
    (net (code "9") (name "ADDR4") (class "Default")
      (node (ref "IC2") (pin "P11") (pinfunction "IO_L22N_7_P11") (pintype "bidirectional"))
    )
    (net (code "10") (name "ADDR5") (class "Default")
      (node (ref "IC2") (pin "P10") (pinfunction "IO_L22P_7_P10") (pintype "bidirectional"))
    )
    (net (code "11") (name "ADDR6") (class "Default")
      (node (ref "IC2") (pin "P8") (pinfunction "IO_L21N_7_P8") (pintype "bidirectional"))
    )
    (net (code "12") (name "ADDR7") (class "Default")
      (node (ref "IC2") (pin "P7") (pinfunction "IO_L21P_7_P7") (pintype "bidirectional"))
    )
    (net (code "13") (name "ADDR8") (class "Default")
      (node (ref "IC2") (pin "P6") (pinfunction "IO_L20N_7_P6") (pintype "bidirectional"))
    )
    (net (code "14") (name "ADDR9") (class "Default")
      (node (ref "IC2") (pin "P5") (pinfunction "IO_L20P_7_P5") (pintype "bidirectional"))
    )
    (net (code "15") (name "ADDR10") (class "Default")
      (node (ref "IC2") (pin "P4") (pinfunction "IOVREF_7_P4") (pintype "bidirectional"))
    )
    (net (code "16") (name "ADDR11") (class "Default")
      (node (ref "IC2") (pin "P2") (pinfunction "IO_L01N_7VRP_7_P2") (pintype "bidirectional"))
    )
    (net (code "17") (name "ADDR12") (class "Default")
      (node (ref "IC2") (pin "P1") (pinfunction "IO_L01P_7VRN_7_P1") (pintype "bidirectional"))
    )
    (net (code "18") (name "ADDR13") (class "Default")
      (node (ref "IC2") (pin "P141") (pinfunction "IO_L01N_0VRP_0_P141") (pintype "bidirectional"))
    )
    (net (code "19") (name "ADDR14") (class "Default")
      (node (ref "IC2") (pin "P140") (pinfunction "IO_L01P_0VRN_0_P140") (pintype "bidirectional"))
    )
    (net (code "20") (name "ADDR15") (class "Default")
      (node (ref "IC2") (pin "P137") (pinfunction "IO_L27N_0_P137") (pintype "bidirectional"))
    )
    (net (code "21") (name "ADDR16") (class "Default")
      (node (ref "IC2") (pin "P135") (pinfunction "IO_L27P_0_P135") (pintype "bidirectional"))
    )
    (net (code "22") (name "ADDR17") (class "Default")
      (node (ref "IC2") (pin "P132") (pinfunction "IO_L30N_0_P132") (pintype "bidirectional"))
    )
    (net (code "23") (name "ADDR18") (class "Default")
      (node (ref "IC2") (pin "P131") (pinfunction "IO_L30P_0_P131") (pintype "bidirectional"))
    )
    (net (code "24") (name "BUSCLK") (class "Default")
      (node (ref "IC2") (pin "P25") (pinfunction "IO_L23P_6_P25") (pintype "bidirectional"))
    )
    (net (code "25") (name "CLK") (class "Default")
      (node (ref "IC2") (pin "P52") (pinfunction "IO_L32P_5GCLK2_P52") (pintype "bidirectional"))
      (node (ref "JP1") (pin "2") (pinfunction "2_2") (pintype "passive"))
    )
    (net (code "26") (name "CLK4MHZ") (class "Default")
      (node (ref "IC2") (pin "P26") (pinfunction "IO_L23N_6_P26") (pintype "bidirectional"))
    )
    (net (code "27") (name "DATA0") (class "Default")
      (node (ref "IC2") (pin "P36") (pinfunction "IO_L01N_6VRP_6_P36") (pintype "bidirectional"))
    )
    (net (code "28") (name "DATA1") (class "Default")
      (node (ref "IC2") (pin "P35") (pinfunction "IO_L01P_6VRN_6_P35") (pintype "bidirectional"))
    )
    (net (code "29") (name "DATA2") (class "Default")
      (node (ref "IC2") (pin "P33") (pinfunction "IO_L20N_6_P33") (pintype "bidirectional"))
    )
    (net (code "30") (name "DATA3") (class "Default")
      (node (ref "IC2") (pin "P32") (pinfunction "IO_L20P_6_P32") (pintype "bidirectional"))
    )
    (net (code "31") (name "DATA4") (class "Default")
      (node (ref "IC2") (pin "P31") (pinfunction "IO_L21N_6_P31") (pintype "bidirectional"))
    )
    (net (code "32") (name "DATA5") (class "Default")
      (node (ref "IC2") (pin "P30") (pinfunction "IO_L21P_6_P30") (pintype "bidirectional"))
    )
    (net (code "33") (name "DATA6") (class "Default")
      (node (ref "IC2") (pin "P28") (pinfunction "IO_L22N_6_P28") (pintype "bidirectional"))
    )
    (net (code "34") (name "DATA7") (class "Default")
      (node (ref "IC2") (pin "P27") (pinfunction "IO_L22P_6_P27") (pintype "bidirectional"))
    )
    (net (code "35") (name "DDIR") (class "Default")
      (node (ref "IC2") (pin "P41") (pinfunction "IO_L01N_5RDWR_B_P41") (pintype "bidirectional"))
    )
    (net (code "36") (name "DISP_DATA0") (class "Default")
      (node (ref "IC2") (pin "P99") (pinfunction "IO_L22P_2_P99") (pintype "bidirectional"))
    )
    (net (code "37") (name "DISP_DATA1") (class "Default")
      (node (ref "IC2") (pin "P100") (pinfunction "IO_L22N_2_P100") (pintype "bidirectional"))
    )
    (net (code "38") (name "DISP_DATA2") (class "Default")
      (node (ref "IC2") (pin "P102") (pinfunction "IO_L21P_2_P102") (pintype "bidirectional"))
    )
    (net (code "39") (name "DISP_DATA3") (class "Default")
      (node (ref "IC2") (pin "P103") (pinfunction "IO_L21N_2_P103") (pintype "bidirectional"))
    )
    (net (code "40") (name "DISP_DATA4") (class "Default")
      (node (ref "IC2") (pin "P104") (pinfunction "IO_L20P_2_P104") (pintype "bidirectional"))
    )
    (net (code "41") (name "DISP_DATA5") (class "Default")
      (node (ref "IC2") (pin "P105") (pinfunction "IO_L20N_2_P105") (pintype "bidirectional"))
    )
    (net (code "42") (name "DISP_DATA6") (class "Default")
      (node (ref "IC2") (pin "P107") (pinfunction "IO_L01P_2VRN_2_P107") (pintype "bidirectional"))
    )
    (net (code "43") (name "DISP_DATA7") (class "Default")
      (node (ref "IC2") (pin "P108") (pinfunction "IO_L01N_2VRP_2_P108") (pintype "bidirectional"))
    )
    (net (code "44") (name "DISP_E1") (class "Default")
      (node (ref "IC2") (pin "P90") (pinfunction "IO_L40N_3VREF_3_P90") (pintype "bidirectional"))
    )
    (net (code "45") (name "DISP_E2") (class "Default")
      (node (ref "IC2") (pin "P89") (pinfunction "IO_L40P_3_P89") (pintype "bidirectional"))
    )
    (net (code "46") (name "DISP_RS") (class "Default")
      (node (ref "IC2") (pin "P93") (pinfunction "IO_L40N_2_P93") (pintype "bidirectional"))
    )
    (net (code "47") (name "DISP_RW") (class "Default")
      (node (ref "IC2") (pin "P92") (pinfunction "IO_L40P_2VREF_2_P92") (pintype "bidirectional"))
    )
    (net (code "48") (name "FPGA_DIN") (class "Default")
      (node (ref "IC1") (pin "1") (pinfunction "DO_1") (pintype "bidirectional"))
      (node (ref "IC2") (pin "P65") (pinfunction "IO_L27N_4DIND0_P65") (pintype "bidirectional"))
    )
    (net (code "49") (name "FPGA_INITB") (class "Default")
      (node (ref "IC1") (pin "8") (pinfunction "OE/RESET_8") (pintype "bidirectional"))
      (node (ref "IC2") (pin "P58") (pinfunction "IO_L31N_4INIT_B_P58") (pintype "bidirectional"))
      (node (ref "R5") (pin "1") (pinfunction "1_1") (pintype "passive"))
    )
    (net (code "50") (name "GND") (class "Default")
      (node (ref "C10") (pin "-") (pinfunction "-_-") (pintype "passive"))
      (node (ref "C104") (pin "2") (pinfunction "2_2") (pintype "passive"))
      (node (ref "C11") (pin "2") (pinfunction "2_2") (pintype "passive"))
      (node (ref "C12") (pin "2") (pinfunction "2_2") (pintype "passive"))
      (node (ref "C13") (pin "-") (pinfunction "-_-") (pintype "passive"))
      (node (ref "C14") (pin "-") (pinfunction "-_-") (pintype "passive"))
      (node (ref "C15") (pin "-") (pinfunction "-_-") (pintype "passive"))
      (node (ref "C16") (pin "-") (pinfunction "-_-") (pintype "passive"))
      (node (ref "C17") (pin "-") (pinfunction "-_-") (pintype "passive"))
      (node (ref "C18") (pin "-") (pinfunction "-_-") (pintype "passive"))
      (node (ref "C19") (pin "2") (pinfunction "2_2") (pintype "passive"))
      (node (ref "C2") (pin "-") (pinfunction "-_-") (pintype "passive"))
      (node (ref "C20") (pin "2") (pinfunction "2_2") (pintype "passive"))
      (node (ref "C21") (pin "2") (pinfunction "2_2") (pintype "passive"))
      (node (ref "C22") (pin "2") (pinfunction "2_2") (pintype "passive"))
      (node (ref "C23") (pin "2") (pinfunction "2_2") (pintype "passive"))
      (node (ref "C24") (pin "2") (pinfunction "2_2") (pintype "passive"))
      (node (ref "C25") (pin "2") (pinfunction "2_2") (pintype "passive"))
      (node (ref "C26") (pin "2") (pinfunction "2_2") (pintype "passive"))
      (node (ref "C27") (pin "2") (pinfunction "2_2") (pintype "passive"))
      (node (ref "C28") (pin "2") (pinfunction "2_2") (pintype "passive"))
      (node (ref "C29") (pin "2") (pinfunction "2_2") (pintype "passive"))
      (node (ref "C3") (pin "2") (pinfunction "2_2") (pintype "passive"))
      (node (ref "C30") (pin "2") (pinfunction "2_2") (pintype "passive"))
      (node (ref "C31") (pin "2") (pinfunction "2_2") (pintype "passive"))
      (node (ref "C32") (pin "2") (pinfunction "2_2") (pintype "passive"))
      (node (ref "C33") (pin "2") (pinfunction "2_2") (pintype "passive"))
      (node (ref "C34") (pin "2") (pinfunction "2_2") (pintype "passive"))
      (node (ref "C35") (pin "2") (pinfunction "2_2") (pintype "passive"))
      (node (ref "C36") (pin "2") (pinfunction "2_2") (pintype "passive"))
      (node (ref "C37") (pin "2") (pinfunction "2_2") (pintype "passive"))
      (node (ref "C38") (pin "2") (pinfunction "2_2") (pintype "passive"))
      (node (ref "C39") (pin "2") (pinfunction "2_2") (pintype "passive"))
      (node (ref "C4") (pin "2") (pinfunction "2_2") (pintype "passive"))
      (node (ref "C40") (pin "2") (pinfunction "2_2") (pintype "passive"))
      (node (ref "C41") (pin "2") (pinfunction "2_2") (pintype "passive"))
      (node (ref "C42") (pin "2") (pinfunction "2_2") (pintype "passive"))
      (node (ref "C43") (pin "2") (pinfunction "2_2") (pintype "passive"))
      (node (ref "C44") (pin "2") (pinfunction "2_2") (pintype "passive"))
      (node (ref "C45") (pin "2") (pinfunction "2_2") (pintype "passive"))
      (node (ref "C46") (pin "2") (pinfunction "2_2") (pintype "passive"))
      (node (ref "C47") (pin "2") (pinfunction "2_2") (pintype "passive"))
      (node (ref "C48") (pin "2") (pinfunction "2_2") (pintype "passive"))
      (node (ref "C49") (pin "2") (pinfunction "2_2") (pintype "passive"))
      (node (ref "C5") (pin "2") (pinfunction "2_2") (pintype "passive"))
      (node (ref "C50") (pin "2") (pinfunction "2_2") (pintype "passive"))
      (node (ref "C6") (pin "-") (pinfunction "-_-") (pintype "passive"))
      (node (ref "C61") (pin "2") (pinfunction "2_2") (pintype "passive"))
      (node (ref "C62") (pin "2") (pinfunction "2_2") (pintype "passive"))
      (node (ref "C7") (pin "2") (pinfunction "2_2") (pintype "passive"))
      (node (ref "C8") (pin "2") (pinfunction "2_2") (pintype "passive"))
      (node (ref "C88") (pin "2") (pinfunction "2_2") (pintype "passive"))
      (node (ref "C89") (pin "2") (pinfunction "2_2") (pintype "passive"))
      (node (ref "C9") (pin "-") (pinfunction "-_-") (pintype "passive"))
      (node (ref "D20") (pin "A") (pinfunction "A_A") (pintype "passive"))
      (node (ref "D21") (pin "A") (pinfunction "A_A") (pintype "passive"))
      (node (ref "IC1") (pin "11") (pinfunction "GND_11") (pintype "bidirectional"))
      (node (ref "IC2") (pin "P101") (pinfunction "GND_P101") (pintype "power_in"))
      (node (ref "IC2") (pin "P114") (pinfunction "GND_P114") (pintype "power_in"))
      (node (ref "IC2") (pin "P117") (pinfunction "GND_P117") (pintype "power_in"))
      (node (ref "IC2") (pin "P136") (pinfunction "GND_P136") (pintype "power_in"))
      (node (ref "IC2") (pin "P139") (pinfunction "GND_P139") (pintype "power_in"))
      (node (ref "IC2") (pin "P142") (pinfunction "HSWAP_EN_P142") (pintype "bidirectional"))
      (node (ref "IC2") (pin "P16") (pinfunction "GND_P16") (pintype "power_in"))
      (node (ref "IC2") (pin "P22") (pinfunction "GND_P22") (pintype "power_in"))
      (node (ref "IC2") (pin "P29") (pinfunction "GND_P29") (pintype "power_in"))
      (node (ref "IC2") (pin "P37") (pinfunction "M1_P37") (pintype "bidirectional"))
      (node (ref "IC2") (pin "P38") (pinfunction "M0_P38") (pintype "bidirectional"))
      (node (ref "IC2") (pin "P39") (pinfunction "M2_P39") (pintype "bidirectional"))
      (node (ref "IC2") (pin "P42") (pinfunction "GND_P42") (pintype "power_in"))
      (node (ref "IC2") (pin "P45") (pinfunction "GND_P45") (pintype "power_in"))
      (node (ref "IC2") (pin "P64") (pinfunction "GND_P64") (pintype "power_in"))
      (node (ref "IC2") (pin "P67") (pinfunction "GND_P67") (pintype "power_in"))
      (node (ref "IC2") (pin "P81") (pinfunction "GND_P81") (pintype "power_in"))
      (node (ref "IC2") (pin "P88") (pinfunction "GND_P88") (pintype "power_in"))
      (node (ref "IC2") (pin "P9") (pinfunction "GND_P9") (pintype "power_in"))
      (node (ref "IC2") (pin "P94") (pinfunction "GND_P94") (pintype "power_in"))
      (node (ref "IC4") (pin "1") (pinfunction "ADJ_1") (pintype "input"))
      (node (ref "IC5") (pin "10") (pinfunction "PGND1_10") (pintype "bidirectional"))
      (node (ref "IC5") (pin "11") (pinfunction "PGND2_11") (pintype "bidirectional"))
      (node (ref "IC5") (pin "15") (pinfunction "EP_15") (pintype "bidirectional"))
      (node (ref "IC5") (pin "3") (pinfunction "SGND_3") (pintype "bidirectional"))
      (node (ref "J11") (pin "1") (pinfunction "KL_1") (pintype "passive"))
      (node (ref "J2") (pin "3") (pinfunction "3_3") (pintype "passive"))
      (node (ref "J8") (pin "SHIELD.1") (pinfunction "SHIELD.1_SHIELD.1") (pintype "bidirectional"))
      (node (ref "J8") (pin "SHIELD.2") (pinfunction "SHIELD.2_SHIELD.2") (pintype "bidirectional"))
      (node (ref "J8") (pin "SHIELD.3") (pinfunction "SHIELD.3_SHIELD.3") (pintype "bidirectional"))
      (node (ref "Q1") (pin "2") (pinfunction "GND_2") (pintype "power_in"))
      (node (ref "Q2") (pin "2") (pinfunction "GND_2") (pintype "power_in"))
      (node (ref "R11") (pin "1") (pinfunction "1_1") (pintype "passive"))
      (node (ref "R113") (pin "1") (pinfunction "1_1") (pintype "passive"))
      (node (ref "R13") (pin "1") (pinfunction "1_1") (pintype "passive"))
    )
    (net (code "51") (name "INTRES") (class "Default")
      (node (ref "IC2") (pin "P119") (pinfunction "IO_L28N_1_P119") (pintype "bidirectional"))
    )
    (net (code "52") (name "IOIN") (class "Default")
      (node (ref "IC2") (pin "P98") (pinfunction "IO_L23N_2VREF_2_P98") (pintype "bidirectional"))
    )
    (net (code "53") (name "IORD") (class "Default")
      (node (ref "IC2") (pin "P113") (pinfunction "IO_L01N_1VRP_1_P113") (pintype "bidirectional"))
    )
    (net (code "54") (name "IOWR") (class "Default")
      (node (ref "IC2") (pin "P112") (pinfunction "IO_L01P_1VRN_1_P112") (pintype "bidirectional"))
    )
    (net (code "55") (name "IO_LOAD") (class "Default")
      (node (ref "IC2") (pin "P97") (pinfunction "IO_L23P_2_P97") (pintype "bidirectional"))
    )
    (net (code "56") (name "IO_OUT1") (class "Default")
      (node (ref "IC2") (pin "P96") (pinfunction "IO_L24N_2_P96") (pintype "bidirectional"))
    )
    (net (code "57") (name "IO_OUT2") (class "Default")
      (node (ref "IC2") (pin "P95") (pinfunction "IO_L24P_2_P95") (pintype "bidirectional"))
    )
    (net (code "58") (name "IRQ") (class "Default")
      (node (ref "IC2") (pin "P130") (pinfunction "IO_L31N_0_P130") (pintype "bidirectional"))
    )
    (net (code "59") (name "IRQS1") (class "Default")
      (node (ref "IC2") (pin "P129") (pinfunction "IO_L31P_0VREF_0_P129") (pintype "bidirectional"))
    )
    (net (code "60") (name "IRQS2") (class "Default")
      (node (ref "IC2") (pin "P128") (pinfunction "IO_L32N_0GCLK7_P128") (pintype "bidirectional"))
    )
    (net (code "61") (name "IRQS3") (class "Default")
      (node (ref "IC2") (pin "P127") (pinfunction "IO_L32P_0GCLK6_P127") (pintype "bidirectional"))
    )
    (net (code "62") (name "IRQS4") (class "Default")
      (node (ref "IC2") (pin "P125") (pinfunction "IO_L32N_1GCLK5_P125") (pintype "bidirectional"))
    )
    (net (code "63") (name "IRQS5") (class "Default")
      (node (ref "IC2") (pin "P124") (pinfunction "IO_L32P_1GCLK4_P124") (pintype "bidirectional"))
    )
    (net (code "64") (name "IRQS6") (class "Default")
      (node (ref "IC2") (pin "P123") (pinfunction "IO_L31N_1VREF_1_P123") (pintype "bidirectional"))
    )
    (net (code "65") (name "IRQS7") (class "Default")
      (node (ref "IC2") (pin "P122") (pinfunction "IO_L31P_1_P122") (pintype "bidirectional"))
    )
    (net (code "66") (name "N_BUSENA") (class "Default")
      (node (ref "IC2") (pin "P40") (pinfunction "IO_L01P_5CS_B_P40") (pintype "bidirectional"))
    )
    (net (code "67") (name "N_CSRAM1") (class "Default")
      (node (ref "IC2") (pin "P46") (pinfunction "IO_L28P_5D7_P46") (pintype "bidirectional"))
    )
    (net (code "68") (name "N_CSRAM2") (class "Default")
      (node (ref "IC2") (pin "P47") (pinfunction "IO_L28N_5D6_P47") (pintype "bidirectional"))
    )
    (net (code "69") (name "N_CSROM") (class "Default")
      (node (ref "IC2") (pin "P44") (pinfunction "IOVREF_5_P44") (pintype "bidirectional"))
    )
    (net (code "70") (name "N_CTS0") (class "Default")
      (node (ref "IC2") (pin "P59") (pinfunction "IO_L30P_4D3_P59") (pintype "bidirectional"))
    )
    (net (code "71") (name "N_CTS1") (class "Default")
      (node (ref "IC2") (pin "P76") (pinfunction "IO_P76") (pintype "bidirectional"))
    )
    (net (code "72") (name "N_DCD0") (class "Default")
      (node (ref "IC2") (pin "P56") (pinfunction "IO_L32N_4GCLK1_P56") (pintype "bidirectional"))
    )
    (net (code "73") (name "N_DCD1") (class "Default")
      (node (ref "IC2") (pin "P70") (pinfunction "IOVREF_4_P70") (pintype "bidirectional"))
    )
    (net (code "74") (name "N_DSR0") (class "Default")
      (node (ref "IC2") (pin "P82") (pinfunction "IO_L22P_3_P82") (pintype "bidirectional"))
    )
    (net (code "75") (name "N_DSR1") (class "Default")
      (node (ref "IC2") (pin "P73") (pinfunction "IO_L01P_3VRN_3_P73") (pintype "bidirectional"))
    )
    (net (code "76") (name "N_DTR0") (class "Default")
      (node (ref "IC2") (pin "P80") (pinfunction "IO_L21N_3_P80") (pintype "bidirectional"))
    )
    (net (code "77") (name "N_DTR1") (class "Default")
      (node (ref "IC2") (pin "P78") (pinfunction "IO_L20N_3_P78") (pintype "bidirectional"))
    )
    (net (code "78") (name "N_HALT") (class "Default")
      (node (ref "IC2") (pin "P118") (pinfunction "IO_L28P_1_P118") (pintype "bidirectional"))
    )
    (net (code "79") (name "N_IOENA0") (class "Default")
      (node (ref "IC2") (pin "P17") (pinfunction "IO_L40P_7_P17") (pintype "bidirectional"))
    )
    (net (code "80") (name "N_IOENA1") (class "Default")
      (node (ref "IC2") (pin "P18") (pinfunction "IO_L40N_7VREF_7_P18") (pintype "bidirectional"))
    )
    (net (code "81") (name "N_IOENA2") (class "Default")
      (node (ref "IC2") (pin "P20") (pinfunction "IO_L40P_6VREF_6_P20") (pintype "bidirectional"))
    )
    (net (code "82") (name "N_LOCAL") (class "Default")
      (node (ref "IC2") (pin "P116") (pinfunction "IO_P116") (pintype "bidirectional"))
    )
    (net (code "83") (name "N_MEMRD") (class "Default")
      (node (ref "IC2") (pin "P50") (pinfunction "IO_L31P_5D5_P50") (pintype "bidirectional"))
    )
    (net (code "84") (name "N_MEMWR") (class "Default")
      (node (ref "IC2") (pin "P51") (pinfunction "IO_L31N_5D4_P51") (pintype "bidirectional"))
    )
    (net (code "85") (name "N_RCOD") (class "Default")
      (node (ref "IC2") (pin "P21") (pinfunction "IO_L40N_6_P21") (pintype "bidirectional"))
    )
    (net (code "86") (name "N_READ") (class "Default")
      (node (ref "IC2") (pin "P23") (pinfunction "IO_L24P_6_P23") (pintype "bidirectional"))
    )
    (net (code "87") (name "N_RESET") (class "Default")
      (node (ref "D22") (pin "3") (pinfunction "C_3") (pintype "passive"))
    )
    (net (code "88") (name "N_RI0") (class "Default")
      (node (ref "IC2") (pin "P60") (pinfunction "IO_L30N_4D2_P60") (pintype "bidirectional"))
    )
    (net (code "89") (name "N_RI1") (class "Default")
      (node (ref "IC2") (pin "P74") (pinfunction "IO_L01N_3VRP_3_P74") (pintype "bidirectional"))
    )
    (net (code "90") (name "N_RTS0") (class "Default")
      (node (ref "IC2") (pin "P68") (pinfunction "IO_L01P_4VRN_4_P68") (pintype "bidirectional"))
    )
    (net (code "91") (name "N_RTS1") (class "Default")
      (node (ref "IC2") (pin "P79") (pinfunction "IO_L21P_3_P79") (pintype "bidirectional"))
    )
    (net (code "92") (name "N_SELCPLD") (class "Default")
      (node (ref "IC2") (pin "P55") (pinfunction "IO_L32P_4GCLK0_P55") (pintype "bidirectional"))
    )
    (net (code "93") (name "N_SWITCHES") (class "Default")
      (node (ref "IC2") (pin "P87") (pinfunction "IO_L24N_3_P87") (pintype "bidirectional"))
    )
    (net (code "94") (name "N_WRITE") (class "Default")
      (node (ref "IC2") (pin "P24") (pinfunction "IO_L24N_6VREF_6_P24") (pintype "bidirectional"))
    )
    (net (code "95") (name "Net-(C13-Pad+)") (class "Default")
      (node (ref "C13") (pin "+") (pinfunction "+_+") (pintype "passive"))
      (node (ref "C14") (pin "+") (pinfunction "+_+") (pintype "passive"))
      (node (ref "C15") (pin "+") (pinfunction "+_+") (pintype "passive"))
      (node (ref "C16") (pin "+") (pinfunction "+_+") (pintype "passive"))
      (node (ref "L1") (pin "2") (pinfunction "2_2") (pintype "passive"))
      (node (ref "R112") (pin "2") (pinfunction "2_2") (pintype "passive"))
      (node (ref "R14") (pin "1") (pinfunction "1_1") (pintype "passive"))
    )
    (net (code "96") (name "Net-(D22-A1)") (class "Default")
      (node (ref "D22") (pin "1") (pinfunction "A1_1") (pintype "passive"))
      (node (ref "D22") (pin "2") (pinfunction "A2_2") (pintype "passive"))
      (node (ref "IC1") (pin "7") (pinfunction "/CF_7") (pintype "bidirectional"))
      (node (ref "IC2") (pin "P143") (pinfunction "PROG_B_P143") (pintype "bidirectional"))
      (node (ref "R4") (pin "2") (pinfunction "2_2") (pintype "passive"))
    )
    (net (code "97") (name "Net-(D23-A1)") (class "Default")
      (node (ref "D23") (pin "1") (pinfunction "A1_1") (pintype "passive"))
      (node (ref "J2") (pin "6") (pinfunction "6_6") (pintype "passive"))
      (node (ref "R116") (pin "1") (pinfunction "1_1") (pintype "passive"))
    )
    (net (code "98") (name "Net-(D23-C)") (class "Default")
      (node (ref "D23") (pin "3") (pinfunction "C_3") (pintype "passive"))
      (node (ref "D24") (pin "1") (pinfunction "A1_1") (pintype "passive"))
    )
    (net (code "99") (name "Net-(D25-C)") (class "Default")
      (node (ref "C104") (pin "1") (pinfunction "1_1") (pintype "passive"))
      (node (ref "D25") (pin "3") (pinfunction "C_3") (pintype "passive"))
      (node (ref "J2") (pin "1") (pinfunction "1_1") (pintype "passive"))
    )
    (net (code "100") (name "Net-(IC1-CLK)") (class "Default")
      (node (ref "IC1") (pin "3") (pinfunction "CLK_3") (pintype "bidirectional"))
      (node (ref "IC2") (pin "P72") (pinfunction "CCLK_P72") (pintype "bidirectional"))
      (node (ref "R155") (pin "1") (pinfunction "1_1") (pintype "passive"))
    )
    (net (code "101") (name "Net-(IC1-TDO)") (class "Default")
      (node (ref "IC1") (pin "17") (pinfunction "TDO_17") (pintype "bidirectional"))
      (node (ref "R3") (pin "2") (pinfunction "2_2") (pintype "passive"))
    )
    (net (code "102") (name "Net-(IC1-{slash}CE)") (class "Default")
      (node (ref "IC1") (pin "10") (pinfunction "/CE_10") (pintype "bidirectional"))
      (node (ref "IC2") (pin "P71") (pinfunction "DONE_P71") (pintype "bidirectional"))
      (node (ref "R6") (pin "2") (pinfunction "2_2") (pintype "passive"))
    )
    (net (code "103") (name "Net-(IC2N-TCK)") (class "Default")
      (node (ref "IC2") (pin "P110") (pinfunction "TCK_P110") (pintype "bidirectional"))
      (node (ref "R2") (pin "1") (pinfunction "1_1") (pintype "passive"))
    )
    (net (code "104") (name "Net-(IC2N-TDI)") (class "Default")
      (node (ref "IC2") (pin "P144") (pinfunction "TDI_P144") (pintype "bidirectional"))
      (node (ref "R3") (pin "1") (pinfunction "1_1") (pintype "passive"))
    )
    (net (code "105") (name "Net-(IC2N-TMS)") (class "Default")
      (node (ref "IC2") (pin "P111") (pinfunction "TMS_P111") (pintype "bidirectional"))
      (node (ref "R1") (pin "1") (pinfunction "1_1") (pintype "passive"))
    )
    (net (code "106") (name "Net-(IC3-ADJ)") (class "Default")
      (node (ref "C7") (pin "1") (pinfunction "1_1") (pintype "passive"))
      (node (ref "IC3") (pin "1") (pinfunction "ADJ_1") (pintype "input"))
      (node (ref "R11") (pin "2") (pinfunction "2_2") (pintype "passive"))
      (node (ref "R12") (pin "1") (pinfunction "1_1") (pintype "passive"))
    )
    (net (code "107") (name "Net-(IC3-OUT)") (class "Default")
      (node (ref "C2") (pin "+") (pinfunction "+_+") (pintype "passive"))
      (node (ref "C4") (pin "1") (pinfunction "1_1") (pintype "passive"))
      (node (ref "IC3") (pin "2") (pinfunction "OUT_2") (pintype "passive"))
      (node (ref "IC3") (pin "4") (pinfunction "OUT1_4") (pintype "passive"))
      (node (ref "IC4") (pin "3") (pinfunction "IN_3") (pintype "input"))
      (node (ref "R12") (pin "2") (pinfunction "2_2") (pintype "passive"))
      (node (ref "R15") (pin "1") (pinfunction "1_1") (pintype "passive"))
    )
    (net (code "108") (name "Net-(IC4-OUT)") (class "Default")
      (node (ref "C6") (pin "+") (pinfunction "+_+") (pintype "passive"))
      (node (ref "IC4") (pin "2") (pinfunction "OUT_2") (pintype "passive"))
      (node (ref "IC4") (pin "4") (pinfunction "OUT1_4") (pintype "passive"))
      (node (ref "R13") (pin "2") (pinfunction "2_2") (pintype "passive"))
      (node (ref "R16") (pin "1") (pinfunction "1_1") (pintype "passive"))
    )
    (net (code "109") (name "Net-(IC5-AVIN)") (class "Default")
      (node (ref "C10") (pin "+") (pinfunction "+_+") (pintype "passive"))
      (node (ref "C11") (pin "1") (pinfunction "1_1") (pintype "passive"))
      (node (ref "C12") (pin "1") (pinfunction "1_1") (pintype "passive"))
      (node (ref "C62") (pin "1") (pinfunction "1_1") (pintype "passive"))
      (node (ref "C9") (pin "+") (pinfunction "+_+") (pintype "passive"))
      (node (ref "IC5") (pin "1") (pinfunction "AVIN_1") (pintype "bidirectional"))
      (node (ref "IC5") (pin "2") (pinfunction "EN_2") (pintype "bidirectional"))
      (node (ref "IC5") (pin "6") (pinfunction "PVIN1_6") (pintype "bidirectional"))
      (node (ref "IC5") (pin "7") (pinfunction "PVIN2_7") (pintype "bidirectional"))
      (node (ref "L2") (pin "1") (pinfunction "1_1") (pintype "passive"))
      (node (ref "L6") (pin "1") (pinfunction "1_1") (pintype "passive"))
    )
    (net (code "110") (name "Net-(IC5-SNS)") (class "Default")
      (node (ref "IC5") (pin "14") (pinfunction "SNS_14") (pintype "bidirectional"))
      (node (ref "R112") (pin "1") (pinfunction "1_1") (pintype "passive"))
      (node (ref "R113") (pin "2") (pinfunction "2_2") (pintype "passive"))
    )
    (net (code "111") (name "Net-(IC5-SS)") (class "Default")
      (node (ref "C8") (pin "1") (pinfunction "1_1") (pintype "passive"))
      (node (ref "IC5") (pin "4") (pinfunction "SS_4") (pintype "bidirectional"))
    )
    (net (code "112") (name "Net-(IC5-SW1)") (class "Default")
      (node (ref "IC5") (pin "8") (pinfunction "SW1_8") (pintype "bidirectional"))
      (node (ref "IC5") (pin "9") (pinfunction "SW2_9") (pintype "bidirectional"))
      (node (ref "L1") (pin "1") (pinfunction "1_1") (pintype "passive"))
    )
    (net (code "113") (name "Net-(J11B-KL)") (class "Default")
      (node (ref "F1") (pin "2") (pinfunction "2_2") (pintype "passive"))
      (node (ref "J11") (pin "2") (pinfunction "KL_2") (pintype "passive"))
    )
    (net (code "114") (name "Net-(Q1-FO)") (class "Default")
      (node (ref "JP1") (pin "3") (pinfunction "3_3") (pintype "passive"))
      (node (ref "Q1") (pin "3") (pinfunction "FO_3") (pintype "output"))
    )
    (net (code "115") (name "Net-(Q1-OE)") (class "Default")
      (node (ref "C88") (pin "1") (pinfunction "1_1") (pintype "passive"))
      (node (ref "L4") (pin "1") (pinfunction "1_1") (pintype "passive"))
      (node (ref "Q1") (pin "1") (pinfunction "OE_1") (pintype "input"))
      (node (ref "Q1") (pin "4") (pinfunction "VCC_4") (pintype "power_in"))
    )
    (net (code "116") (name "Net-(Q2-FO)") (class "Default")
      (node (ref "JP1") (pin "1") (pinfunction "1_1") (pintype "passive"))
      (node (ref "Q2") (pin "3") (pinfunction "FO_3") (pintype "output"))
    )
    (net (code "117") (name "Net-(Q2-OE)") (class "Default")
      (node (ref "C89") (pin "1") (pinfunction "1_1") (pintype "passive"))
      (node (ref "L5") (pin "1") (pinfunction "1_1") (pintype "passive"))
      (node (ref "Q2") (pin "1") (pinfunction "OE_1") (pintype "input"))
      (node (ref "Q2") (pin "4") (pinfunction "VCC_4") (pintype "power_in"))
    )
    (net (code "118") (name "PS2_CLK_I") (class "Default")
      (node (ref "IC2") (pin "P86") (pinfunction "IO_L24P_3_P86") (pintype "bidirectional"))
    )
    (net (code "119") (name "PS2_CLK_O") (class "Default")
      (node (ref "IC2") (pin "P85") (pinfunction "IO_L23N_3_P85") (pintype "bidirectional"))
    )
    (net (code "120") (name "PS2_DAT_I") (class "Default")
      (node (ref "IC2") (pin "P84") (pinfunction "IO_L23P_3VREF_3_P84") (pintype "bidirectional"))
    )
    (net (code "121") (name "PS2_DAT_O") (class "Default")
      (node (ref "IC2") (pin "P83") (pinfunction "IO_L22N_3_P83") (pintype "bidirectional"))
    )
    (net (code "122") (name "RXD0") (class "Default")
      (node (ref "IC2") (pin "P57") (pinfunction "IO_L31P_4DOUTBUSY_P57") (pintype "bidirectional"))
    )
    (net (code "123") (name "RXD1") (class "Default")
      (node (ref "IC2") (pin "P69") (pinfunction "IO_L01N_4VRP_4_P69") (pintype "bidirectional"))
    )
    (net (code "124") (name "TCK") (class "Default")
      (node (ref "IC1") (pin "6") (pinfunction "TCK_6") (pintype "bidirectional"))
      (node (ref "J2") (pin "5") (pinfunction "5_5") (pintype "passive"))
      (node (ref "R2") (pin "2") (pinfunction "2_2") (pintype "passive"))
    )
    (net (code "125") (name "TDI") (class "Default")
      (node (ref "IC1") (pin "4") (pinfunction "TDI_4") (pintype "bidirectional"))
      (node (ref "J2") (pin "4") (pinfunction "4_4") (pintype "passive"))
    )
    (net (code "126") (name "TDO") (class "Default")
      (node (ref "D24") (pin "3") (pinfunction "C_3") (pintype "passive"))
      (node (ref "IC2") (pin "P109") (pinfunction "TDO_P109") (pintype "bidirectional"))
      (node (ref "R154") (pin "1") (pinfunction "1_1") (pintype "passive"))
    )
    (net (code "127") (name "TMS") (class "Default")
      (node (ref "IC1") (pin "5") (pinfunction "TMS_5") (pintype "bidirectional"))
      (node (ref "J2") (pin "2") (pinfunction "2_2") (pintype "passive"))
      (node (ref "R1") (pin "2") (pinfunction "2_2") (pintype "passive"))
    )
    (net (code "128") (name "TXD0") (class "Default")
      (node (ref "IC2") (pin "P63") (pinfunction "IO_L27P_4D1_P63") (pintype "bidirectional"))
    )
    (net (code "129") (name "TXD1") (class "Default")
      (node (ref "IC2") (pin "P77") (pinfunction "IO_L20P_3_P77") (pintype "bidirectional"))
    )
    (net (code "130") (name "unconnected-(D23-A2-Pad2)") (class "Default")
      (node (ref "D23") (pin "2") (pinfunction "A2_2") (pintype "passive"))
    )
    (net (code "131") (name "unconnected-(D24-A2-Pad2)") (class "Default")
      (node (ref "D24") (pin "2") (pinfunction "A2_2") (pintype "passive"))
    )
    (net (code "132") (name "unconnected-(IC1-NC.1-Pad2)") (class "Default")
      (node (ref "IC1") (pin "2") (pinfunction "NC.1_2") (pintype "bidirectional"))
    )
    (net (code "133") (name "unconnected-(IC1-NC.2-Pad9)") (class "Default")
      (node (ref "IC1") (pin "9") (pinfunction "NC.2_9") (pintype "bidirectional"))
    )
    (net (code "134") (name "unconnected-(IC1-NC.3-Pad12)") (class "Default")
      (node (ref "IC1") (pin "12") (pinfunction "NC.3_12") (pintype "bidirectional"))
    )
    (net (code "135") (name "unconnected-(IC1-NC.4-Pad14)") (class "Default")
      (node (ref "IC1") (pin "14") (pinfunction "NC.4_14") (pintype "bidirectional"))
    )
    (net (code "136") (name "unconnected-(IC1-NC.5-Pad15)") (class "Default")
      (node (ref "IC1") (pin "15") (pinfunction "NC.5_15") (pintype "bidirectional"))
    )
    (net (code "137") (name "unconnected-(IC1-NC.6-Pad16)") (class "Default")
      (node (ref "IC1") (pin "16") (pinfunction "NC.6_16") (pintype "bidirectional"))
    )
    (net (code "138") (name "unconnected-(IC1-{slash}CEO-Pad13)") (class "Default")
      (node (ref "IC1") (pin "13") (pinfunction "/CEO_13") (pintype "bidirectional"))
    )
    (net (code "139") (name "unconnected-(IC2I-IO_L32N_5GCLK3-PadP53)") (class "Default")
      (node (ref "IC2") (pin "P53") (pinfunction "IO_L32N_5GCLK3_P53") (pintype "bidirectional"))
    )
    (net (code "140") (name "unconnected-(IC5-NC1-Pad5)") (class "Default")
      (node (ref "IC5") (pin "5") (pinfunction "NC1_5") (pintype "bidirectional"))
    )
    (net (code "141") (name "unconnected-(IC5-NC2-Pad12)") (class "Default")
      (node (ref "IC5") (pin "12") (pinfunction "NC2_12") (pintype "bidirectional"))
    )
    (net (code "142") (name "unconnected-(IC5-NC3-Pad13)") (class "Default")
      (node (ref "IC5") (pin "13") (pinfunction "NC3_13") (pintype "bidirectional"))
    )
    (net (code "143") (name "unconnected-(J8-Pad1)") (class "Default")
      (node (ref "J8") (pin "1") (pinfunction "1_1") (pintype "passive"))
    )
    (net (code "144") (name "unconnected-(J8-Pad2)") (class "Default")
      (node (ref "J8") (pin "2") (pinfunction "2_2") (pintype "passive"))
    )
    (net (code "145") (name "unconnected-(J8-Pad3)") (class "Default")
      (node (ref "J8") (pin "3") (pinfunction "3_3") (pintype "passive"))
    )
    (net (code "146") (name "unconnected-(J8-Pad4)") (class "Default")
      (node (ref "J8") (pin "4") (pinfunction "4_4") (pintype "passive"))
    )
    (net (code "147") (name "unconnected-(J8-Pad5)") (class "Default")
      (node (ref "J8") (pin "5") (pinfunction "5_5") (pintype "passive"))
    )
    (net (code "148") (name "unconnected-(J8-Pad6)") (class "Default")
      (node (ref "J8") (pin "6") (pinfunction "6_6") (pintype "passive"))
    )
  )
)
